# zx80_SD_12_smd_build005.net
KiCad netlist of a schematic drawn in EAGLE
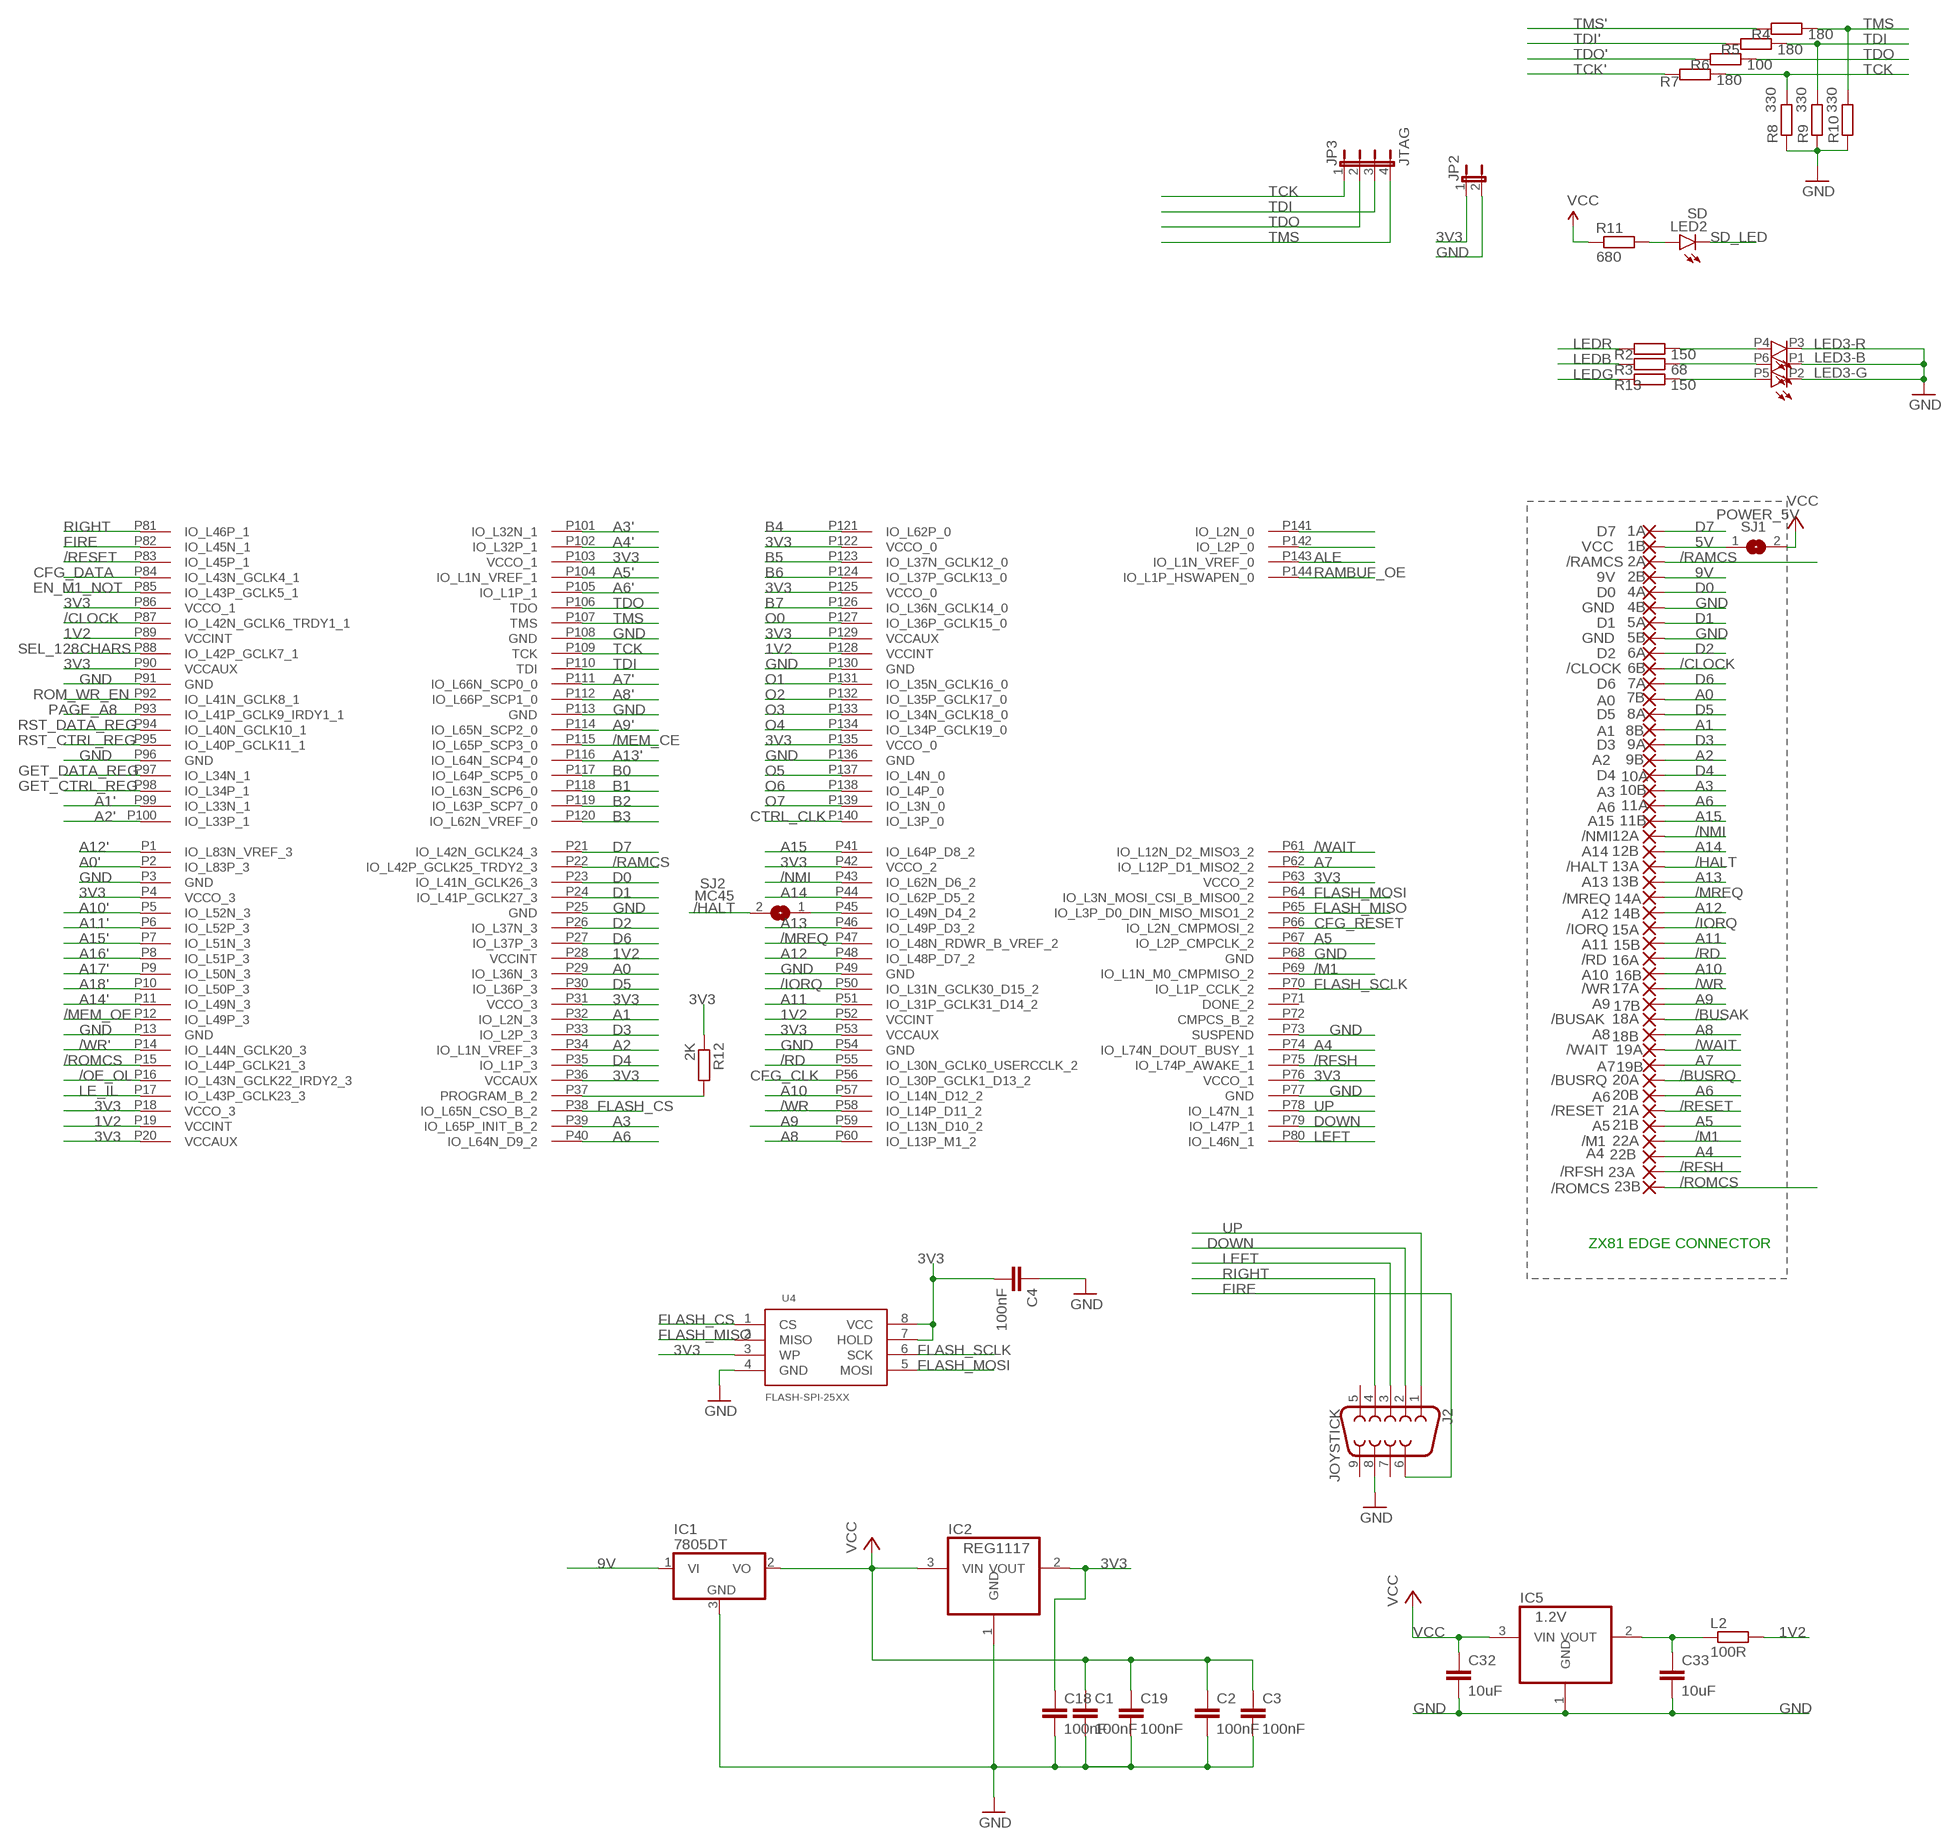
[diagram p0: schematic, sheet 1, part 1 of 2]
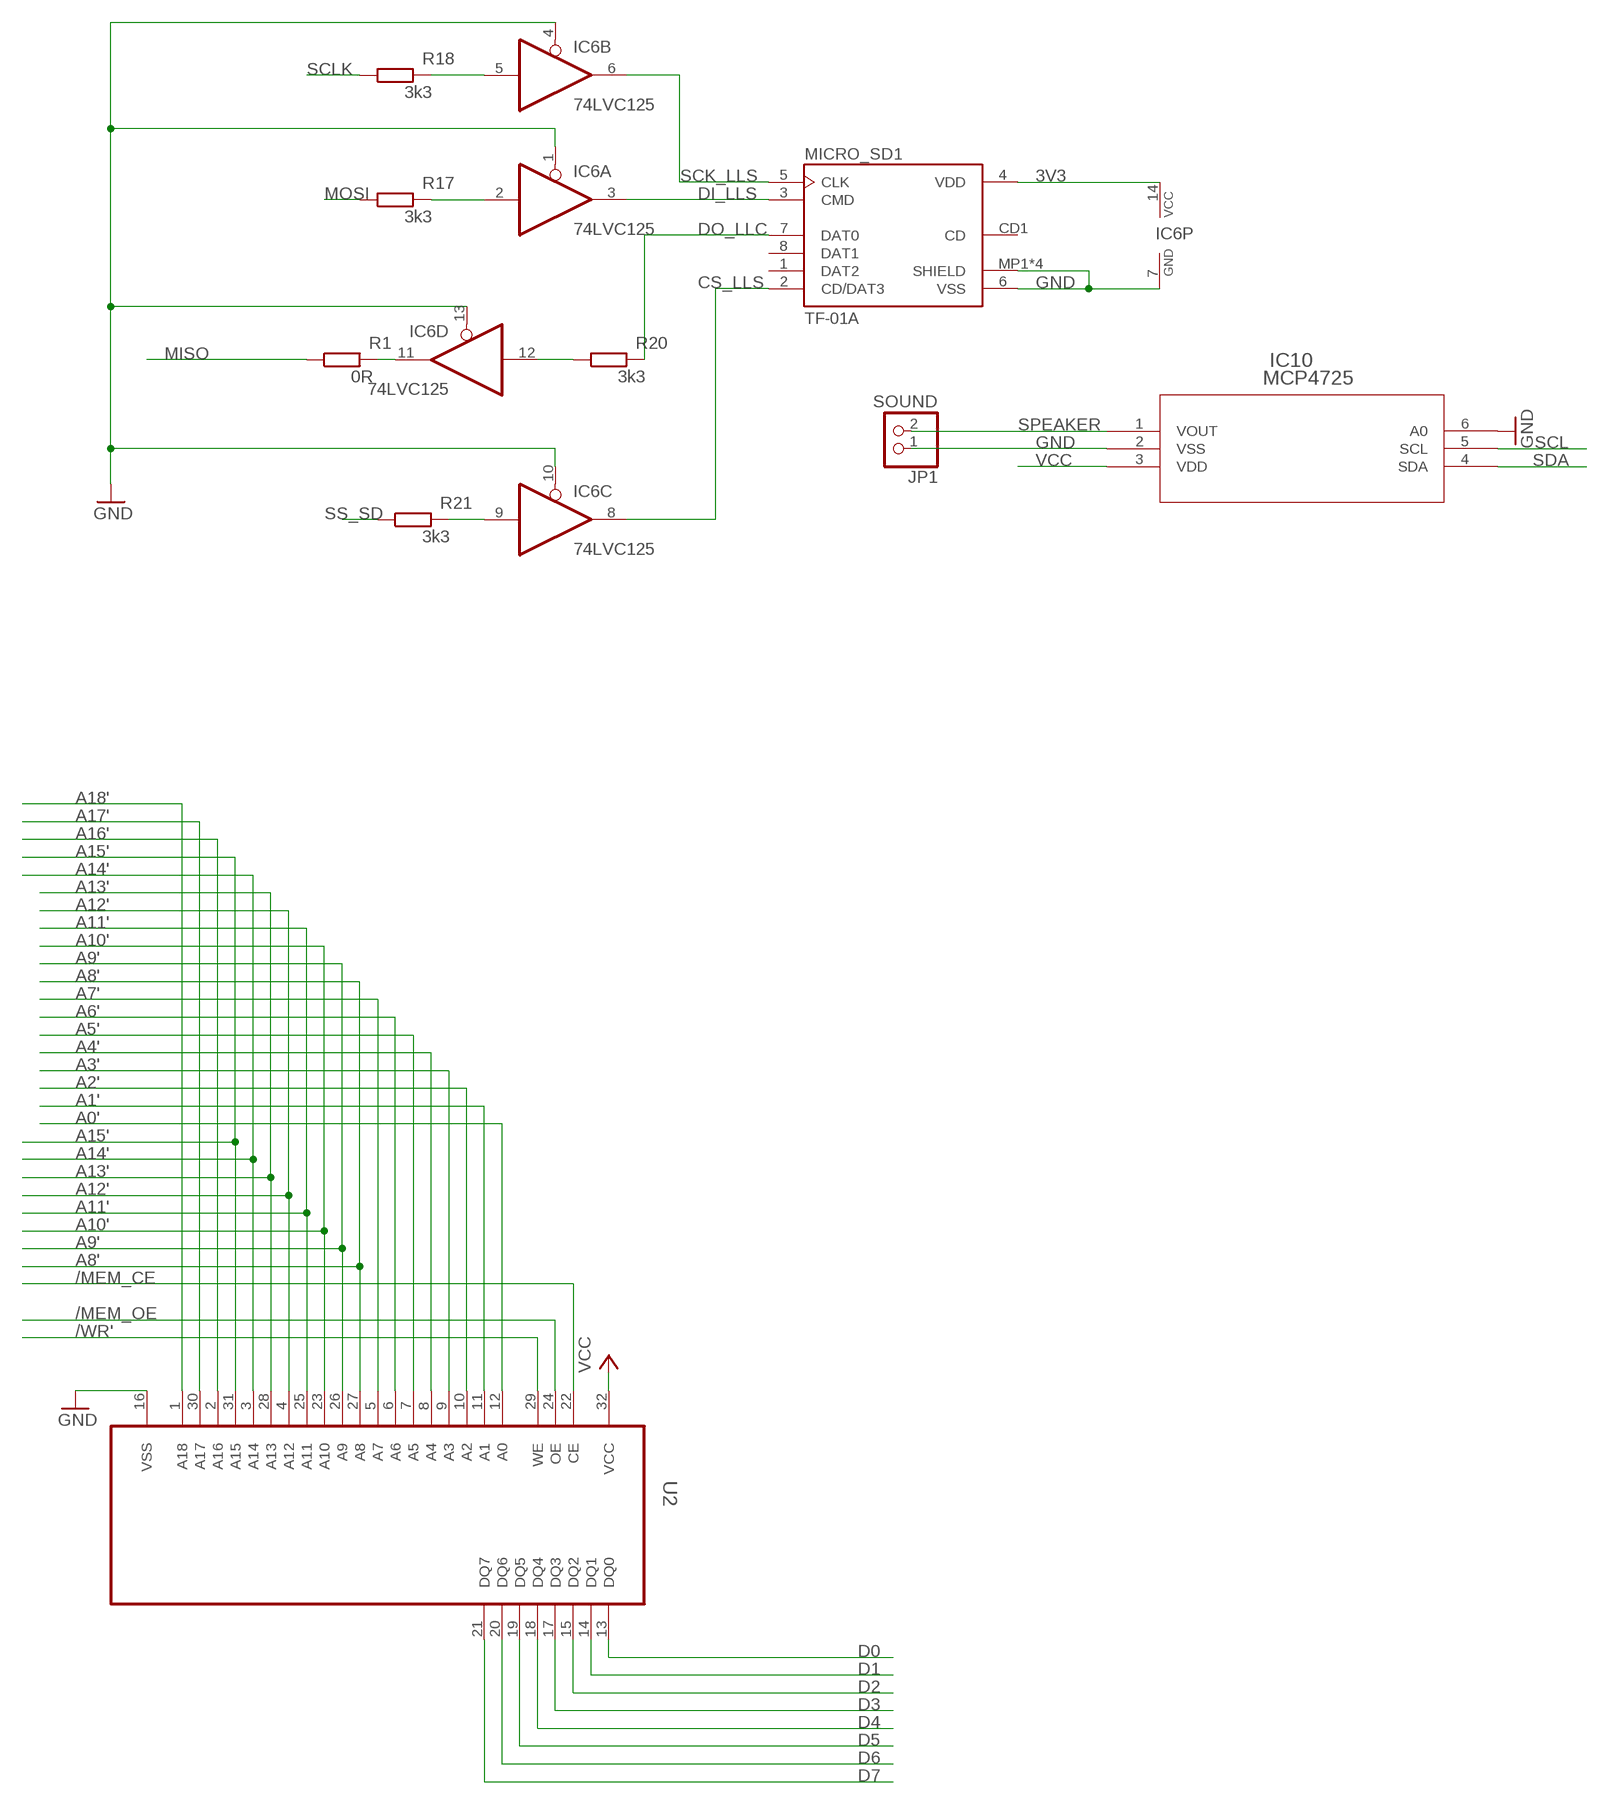
[diagram p1: schematic, sheet 1, part 2 of 2]
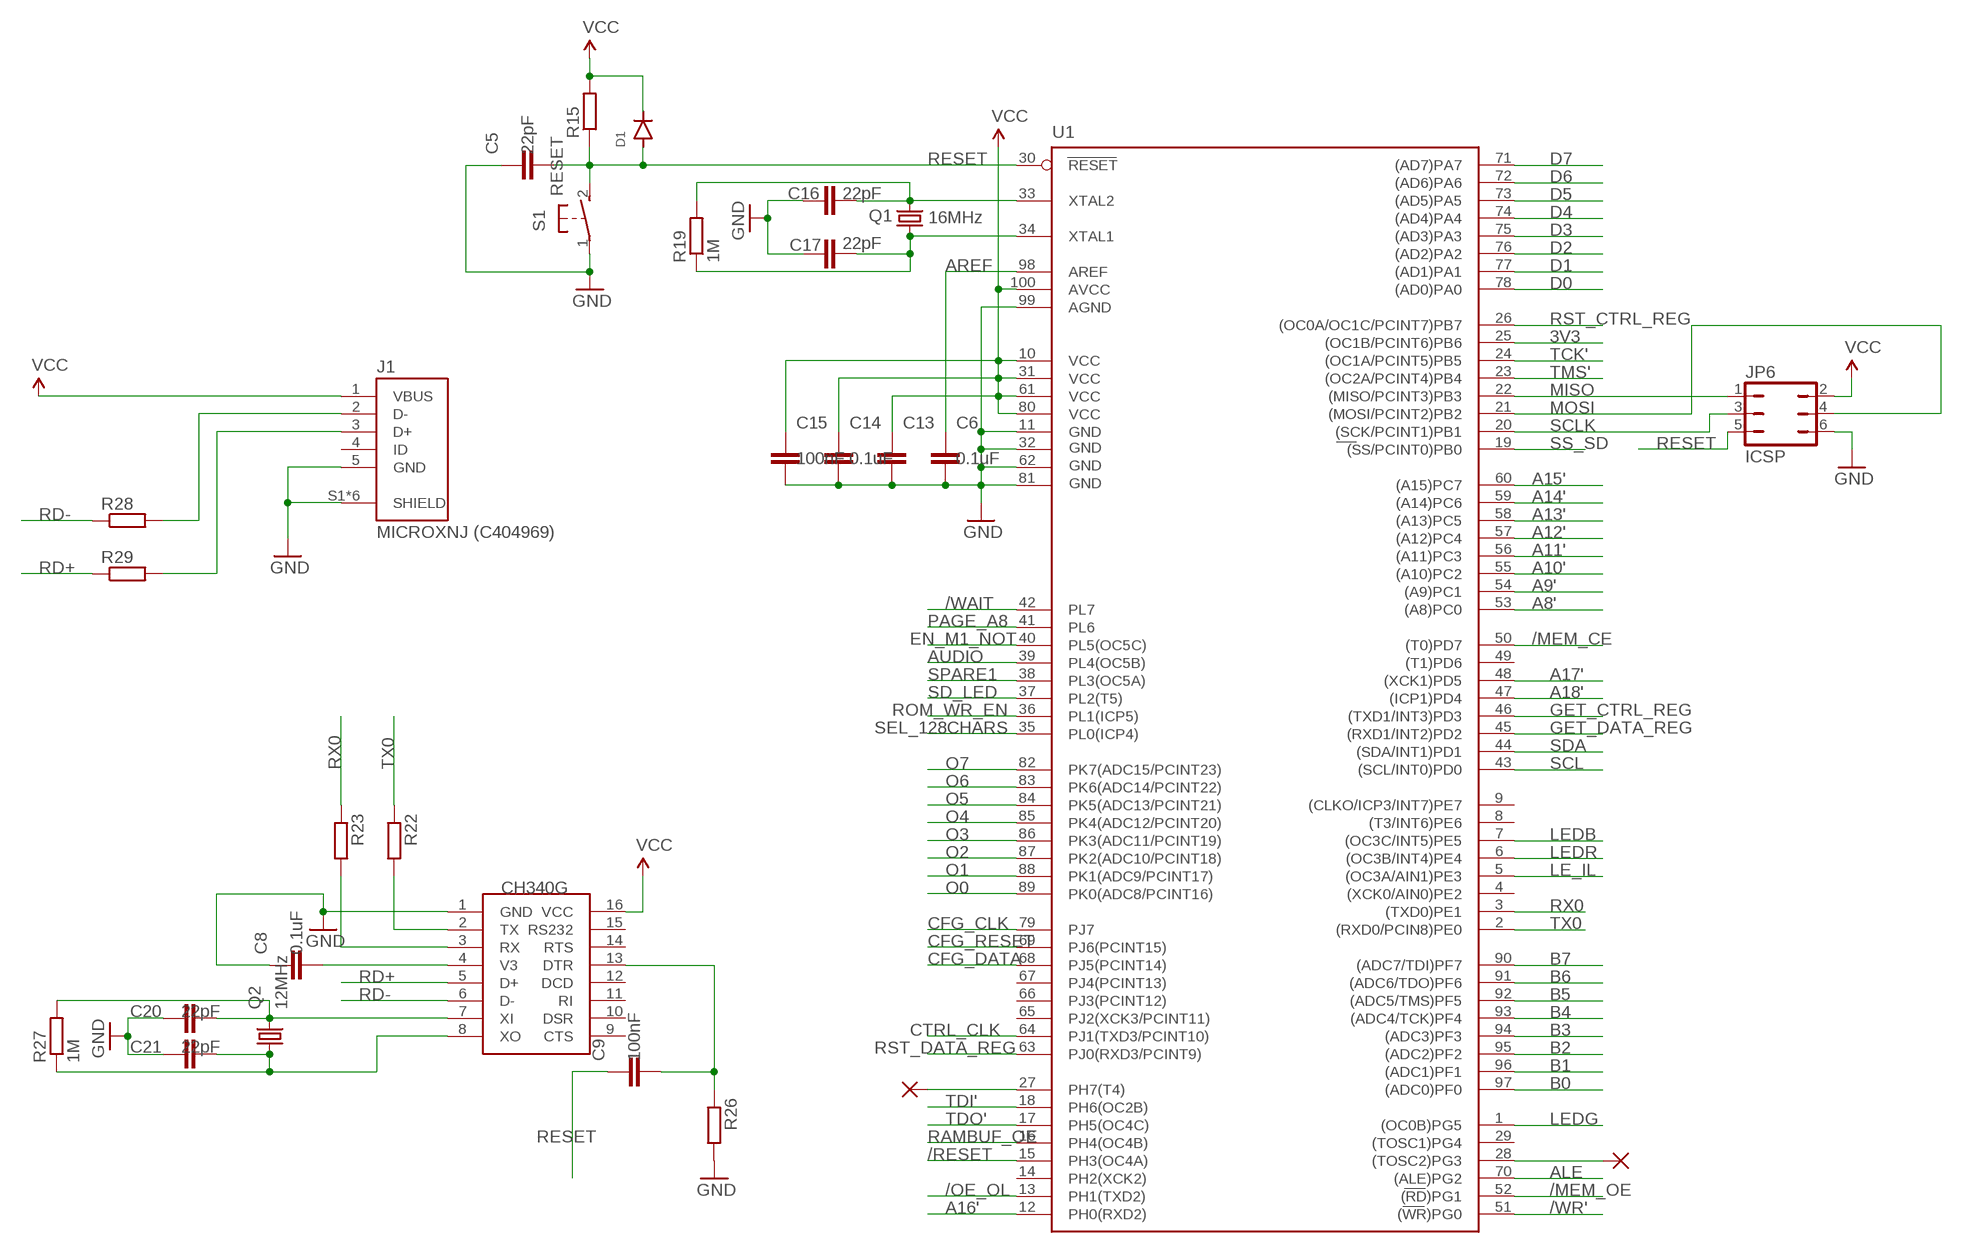
[diagram p2: schematic, sheet 2]

(export (version "E")
  (design (tool "Eeschema 10.0.6"))
  (components
    (comp (ref "1A")
      (value "D7")
      (footprint "eagle-import:EDGEPIN")
      (libsource (lib "eagle-import") (part "SMD2EDGEPIN"))
    )
    (comp (ref "1B")
      (value "VCC")
      (footprint "eagle-import:EDGEPIN")
      (libsource (lib "eagle-import") (part "SMD2EDGEPIN"))
    )
    (comp (ref "2A")
      (value "/RAMCS")
      (footprint "eagle-import:EDGEPIN")
      (libsource (lib "eagle-import") (part "SMD2EDGEPIN"))
    )
    (comp (ref "2B")
      (value "9V")
      (footprint "eagle-import:EDGEPIN")
      (libsource (lib "eagle-import") (part "SMD2EDGEPIN"))
    )
    (comp (ref "4A")
      (value "D0")
      (footprint "eagle-import:EDGEPIN")
      (libsource (lib "eagle-import") (part "SMD2EDGEPIN"))
    )
    (comp (ref "4B")
      (value "GND")
      (footprint "eagle-import:EDGEPIN")
      (libsource (lib "eagle-import") (part "SMD2EDGEPIN"))
    )
    (comp (ref "5A")
      (value "D1")
      (footprint "eagle-import:EDGEPIN")
      (libsource (lib "eagle-import") (part "SMD2EDGEPIN"))
    )
    (comp (ref "5B")
      (value "GND")
      (footprint "eagle-import:EDGEPIN")
      (libsource (lib "eagle-import") (part "SMD2EDGEPIN"))
    )
    (comp (ref "6A")
      (value "D2")
      (footprint "eagle-import:EDGEPIN")
      (libsource (lib "eagle-import") (part "SMD2EDGEPIN"))
    )
    (comp (ref "6B")
      (value "/CLOCK")
      (footprint "eagle-import:EDGEPIN")
      (libsource (lib "eagle-import") (part "SMD2EDGEPIN"))
    )
    (comp (ref "7A")
      (value "D6")
      (footprint "eagle-import:EDGEPIN")
      (libsource (lib "eagle-import") (part "SMD2EDGEPIN"))
    )
    (comp (ref "7B")
      (value "A0")
      (footprint "eagle-import:EDGEPIN")
      (libsource (lib "eagle-import") (part "SMD2EDGEPIN"))
    )
    (comp (ref "8A")
      (value "D5")
      (footprint "eagle-import:EDGEPIN")
      (libsource (lib "eagle-import") (part "SMD2EDGEPIN"))
    )
    (comp (ref "8B")
      (value "A1")
      (footprint "eagle-import:EDGEPIN")
      (libsource (lib "eagle-import") (part "SMD2EDGEPIN"))
    )
    (comp (ref "9A")
      (value "D3")
      (footprint "eagle-import:EDGEPIN")
      (libsource (lib "eagle-import") (part "SMD2EDGEPIN"))
    )
    (comp (ref "9B")
      (value "A2")
      (footprint "eagle-import:EDGEPIN")
      (libsource (lib "eagle-import") (part "SMD2EDGEPIN"))
    )
    (comp (ref "10A")
      (value "D4")
      (footprint "eagle-import:EDGEPIN")
      (libsource (lib "eagle-import") (part "SMD2EDGEPIN"))
    )
    (comp (ref "10B")
      (value "A3")
      (footprint "eagle-import:EDGEPIN")
      (libsource (lib "eagle-import") (part "SMD2EDGEPIN"))
    )
    (comp (ref "11A")
      (value "A6")
      (footprint "eagle-import:EDGEPIN")
      (libsource (lib "eagle-import") (part "SMD2EDGEPIN"))
    )
    (comp (ref "11B")
      (value "A15")
      (footprint "eagle-import:EDGEPIN")
      (libsource (lib "eagle-import") (part "SMD2EDGEPIN"))
    )
    (comp (ref "12A")
      (value "/NMI")
      (footprint "eagle-import:EDGEPIN")
      (libsource (lib "eagle-import") (part "SMD2EDGEPIN"))
    )
    (comp (ref "12B")
      (value "A14")
      (footprint "eagle-import:EDGEPIN")
      (libsource (lib "eagle-import") (part "SMD2EDGEPIN"))
    )
    (comp (ref "13A")
      (value "/HALT")
      (footprint "eagle-import:EDGEPIN")
      (libsource (lib "eagle-import") (part "SMD2EDGEPIN"))
    )
    (comp (ref "13B")
      (value "A13")
      (footprint "eagle-import:EDGEPIN")
      (libsource (lib "eagle-import") (part "SMD2EDGEPIN"))
    )
    (comp (ref "14A")
      (value "/MREQ")
      (footprint "eagle-import:EDGEPIN")
      (libsource (lib "eagle-import") (part "SMD2EDGEPIN"))
    )
    (comp (ref "14B")
      (value "A12")
      (footprint "eagle-import:EDGEPIN")
      (libsource (lib "eagle-import") (part "SMD2EDGEPIN"))
    )
    (comp (ref "15A")
      (value "/IORQ")
      (footprint "eagle-import:EDGEPIN")
      (libsource (lib "eagle-import") (part "SMD2EDGEPIN"))
    )
    (comp (ref "15B")
      (value "A11")
      (footprint "eagle-import:EDGEPIN")
      (libsource (lib "eagle-import") (part "SMD2EDGEPIN"))
    )
    (comp (ref "16A")
      (value "/RD")
      (footprint "eagle-import:EDGEPIN")
      (libsource (lib "eagle-import") (part "SMD2EDGEPIN"))
    )
    (comp (ref "16B")
      (value "A10")
      (footprint "eagle-import:EDGEPIN")
      (libsource (lib "eagle-import") (part "SMD2EDGEPIN"))
    )
    (comp (ref "17A")
      (value "/WR")
      (footprint "eagle-import:EDGEPIN")
      (libsource (lib "eagle-import") (part "SMD2EDGEPIN"))
    )
    (comp (ref "17B")
      (value "A9")
      (footprint "eagle-import:EDGEPIN")
      (libsource (lib "eagle-import") (part "SMD2EDGEPIN"))
    )
    (comp (ref "18A")
      (value "/BUSAK")
      (footprint "eagle-import:EDGEPIN")
      (libsource (lib "eagle-import") (part "SMD2EDGEPIN"))
    )
    (comp (ref "18B")
      (value "A8")
      (footprint "eagle-import:EDGEPIN")
      (libsource (lib "eagle-import") (part "SMD2EDGEPIN"))
    )
    (comp (ref "19A")
      (value "/WAIT")
      (footprint "eagle-import:EDGEPIN")
      (libsource (lib "eagle-import") (part "SMD2EDGEPIN"))
    )
    (comp (ref "19B")
      (value "A7")
      (footprint "eagle-import:EDGEPIN")
      (libsource (lib "eagle-import") (part "SMD2EDGEPIN"))
    )
    (comp (ref "20A")
      (value "/BUSRQ")
      (footprint "eagle-import:EDGEPIN")
      (libsource (lib "eagle-import") (part "SMD2EDGEPIN"))
    )
    (comp (ref "20B")
      (value "A6")
      (footprint "eagle-import:EDGEPIN")
      (libsource (lib "eagle-import") (part "SMD2EDGEPIN"))
    )
    (comp (ref "21A")
      (value "/RESET")
      (footprint "eagle-import:EDGEPIN")
      (libsource (lib "eagle-import") (part "SMD2EDGEPIN"))
    )
    (comp (ref "21B")
      (value "A5")
      (footprint "eagle-import:EDGEPIN")
      (libsource (lib "eagle-import") (part "SMD2EDGEPIN"))
    )
    (comp (ref "22A")
      (value "/M1")
      (footprint "eagle-import:EDGEPIN")
      (libsource (lib "eagle-import") (part "SMD2EDGEPIN"))
    )
    (comp (ref "22B")
      (value "A4")
      (footprint "eagle-import:EDGEPIN")
      (libsource (lib "eagle-import") (part "SMD2EDGEPIN"))
    )
    (comp (ref "23A")
      (value "/RFSH")
      (footprint "eagle-import:EDGEPIN")
      (libsource (lib "eagle-import") (part "SMD2EDGEPIN"))
    )
    (comp (ref "23B")
      (value "/ROMCS")
      (footprint "eagle-import:EDGEPIN")
      (libsource (lib "eagle-import") (part "SMD2EDGEPIN"))
    )
    (comp (ref "C1")
      (value "100nF")
      (footprint "eagle-import:C0603")
      (libsource (lib "eagle-import") (part "rcl_334_C-EUC0603"))
    )
    (comp (ref "C2")
      (value "100nF")
      (footprint "eagle-import:C0603")
      (libsource (lib "eagle-import") (part "rcl_334_C-EUC0603"))
    )
    (comp (ref "C3")
      (value "100nF")
      (footprint "eagle-import:C0603")
      (libsource (lib "eagle-import") (part "rcl_334_C-EUC0603"))
    )
    (comp (ref "C4")
      (value "100nF")
      (footprint "eagle-import:C0603K")
      (libsource (lib "eagle-import") (part "C-EUC0603K"))
    )
    (comp (ref "C18")
      (value "100nF")
      (footprint "eagle-import:C0603")
      (libsource (lib "eagle-import") (part "rcl_334_C-EUC0603"))
    )
    (comp (ref "C19")
      (value "100nF")
      (footprint "eagle-import:C0603")
      (libsource (lib "eagle-import") (part "rcl_334_C-EUC0603"))
    )
    (comp (ref "C32")
      (value "10uF")
      (footprint "eagle-import:C0603K")
      (libsource (lib "eagle-import") (part "C-EUC0603K"))
    )
    (comp (ref "C33")
      (value "10uF")
      (footprint "eagle-import:C0603K")
      (libsource (lib "eagle-import") (part "C-EUC0603K"))
    )
    (comp (ref "IC1")
      (value "7805DT")
      (footprint "eagle-import:TO252")
      (libsource (lib "eagle-import") (part "78DT05"))
    )
    (comp (ref "IC2")
      (value "REG1117")
      (footprint "eagle-import:SOT223")
      (libsource (lib "eagle-import") (part "burr-brown_41243815_REG1117"))
    )
    (comp (ref "IC5")
      (value "1.2V")
      (footprint "eagle-import:SOT223")
      (fields (field (name "MPN") "REG1117"))
      (libsource (lib "eagle-import") (part "REG1117"))
    )
    (comp (ref "IC6")
      (value "74LVC125")
      (footprint "eagle-import:SO14")
      (libsource (lib "eagle-import") (part "74125DLS"))
    )
    (comp (ref "IC10")
      (value "MCP4725")
      (footprint "eagle-import:SOT-23-6_MC")
      (fields (field (name "MF") "Microchip") (field (name "MP") "MCP4725A2T-E/CH"))
      (libsource (lib "eagle-import") (part "MCP4725A2T-E/CH"))
    )
    (comp (ref "J2")
      (value "JOYSTICK")
      (footprint "eagle-import:DB9_MALE")
      (libsource (lib "eagle-import") (part "DB9MALE"))
    )
    (comp (ref "JP1")
      (value "SOUND")
      (footprint "eagle-import:1X02")
      (libsource (lib "eagle-import") (part "PINHD-1X2"))
    )
    (comp (ref "JP2")
      (value "JP1E")
      (footprint "eagle-import:JP1")
      (libsource (lib "eagle-import") (part "JP1E"))
    )
    (comp (ref "JP3")
      (value "JTAG")
      (footprint "eagle-import:JP4")
      (libsource (lib "eagle-import") (part "JP4E"))
    )
    (comp (ref "L2")
      (value "100R")
      (footprint "eagle-import:R0603")
      (libsource (lib "eagle-import") (part "R-EU_R0603"))
    )
    (comp (ref "LED2")
      (value "SD")
      (footprint "eagle-import:CHIPLED_0603")
      (libsource (lib "eagle-import") (part "LEDCHIPLED_0603"))
    )
    (comp (ref "LED3")
      (value "STATUS")
      (footprint "eagle-import:3535-PLCC6")
      (libsource (lib "eagle-import") (part "3535RGB3535RGB"))
    )
    (comp (ref "MICRO_SD1")
      (value "TF-01A")
      (footprint "eagle-import:TF-01A")
      (fields (field (name "MF") "HRO Electronics Co., Ltd."))
      (libsource (lib "eagle-import") (part "TF-01A"))
    )
    (comp (ref "R1")
      (value "0R")
      (footprint "eagle-import:R0603")
      (libsource (lib "eagle-import") (part "R-EU_R0603"))
    )
    (comp (ref "R2")
      (value "150")
      (footprint "eagle-import:R0603")
      (libsource (lib "eagle-import") (part "rcl_334_R-EU_R0603"))
    )
    (comp (ref "R3")
      (value "68")
      (footprint "eagle-import:R0603")
      (libsource (lib "eagle-import") (part "rcl_334_R-EU_R0603"))
    )
    (comp (ref "R4")
      (value "180")
      (footprint "eagle-import:R0603")
      (libsource (lib "eagle-import") (part "rcl_334_R-EU_R0603"))
    )
    (comp (ref "R5")
      (value "180")
      (footprint "eagle-import:R0603")
      (libsource (lib "eagle-import") (part "rcl_334_R-EU_R0603"))
    )
    (comp (ref "R6")
      (value "100")
      (footprint "eagle-import:R0603")
      (libsource (lib "eagle-import") (part "rcl_334_R-EU_R0603"))
    )
    (comp (ref "R7")
      (value "180")
      (footprint "eagle-import:R0603")
      (libsource (lib "eagle-import") (part "rcl_334_R-EU_R0603"))
    )
    (comp (ref "R8")
      (value "330")
      (footprint "eagle-import:R0603")
      (libsource (lib "eagle-import") (part "rcl_334_R-EU_R0603"))
    )
    (comp (ref "R9")
      (value "330")
      (footprint "eagle-import:R0603")
      (libsource (lib "eagle-import") (part "rcl_334_R-EU_R0603"))
    )
    (comp (ref "R10")
      (value "330")
      (footprint "eagle-import:R0603")
      (libsource (lib "eagle-import") (part "rcl_334_R-EU_R0603"))
    )
    (comp (ref "R11")
      (value "680")
      (footprint "eagle-import:R0603")
      (libsource (lib "eagle-import") (part "R-EU_R0603"))
    )
    (comp (ref "R12")
      (value "2K")
      (footprint "eagle-import:R0603")
      (libsource (lib "eagle-import") (part "rcl_334_R-EU_R0603"))
    )
    (comp (ref "R13")
      (value "150")
      (footprint "eagle-import:R0603")
      (libsource (lib "eagle-import") (part "rcl_334_R-EU_R0603"))
    )
    (comp (ref "R17")
      (value "3k3")
      (footprint "eagle-import:R0603")
      (libsource (lib "eagle-import") (part "R-EU_R0603"))
    )
    (comp (ref "R18")
      (value "3k3")
      (footprint "eagle-import:R0603")
      (libsource (lib "eagle-import") (part "R-EU_R0603"))
    )
    (comp (ref "R20")
      (value "3k3")
      (footprint "eagle-import:R0603")
      (libsource (lib "eagle-import") (part "R-EU_R0603"))
    )
    (comp (ref "R21")
      (value "3k3")
      (footprint "eagle-import:R0603")
      (libsource (lib "eagle-import") (part "R-EU_R0603"))
    )
    (comp (ref "SJ1")
      (value "POWER_5V")
      (footprint "eagle-import:SJ")
      (libsource (lib "eagle-import") (part "SJ"))
    )
    (comp (ref "SJ2")
      (value "MC45")
      (footprint "eagle-import:SJ")
      (libsource (lib "eagle-import") (part "SJ"))
    )
    (comp (ref "U$1")
      (value "XC6SLX9-2TQG144C")
      (footprint "eagle-import:TQ144")
      (fields (field (name "MF") "Xilinx Inc."))
      (libsource (lib "eagle-import") (part "XC6SLX9-2TQG144C"))
    )
    (comp (ref "U2")
      (value "AS6C4008")
      (footprint "eagle-import:SOP32-5")
      (libsource (lib "eagle-import") (part "AS6C4008-55SINSOP5"))
    )
    (comp (ref "U4")
      (value "FLASH-SPI-25XX")
      (footprint "eagle-import:SO08-EIAJ")
      (libsource (lib "eagle-import") (part "FLASH-SPI-25XXSMD1"))
    )
    (comp (ref "C5")
      (value "22pF")
      (footprint "eagle-import:C0603")
      (libsource (lib "eagle-import") (part "rcl_334_C-EUC0603"))
    )
    (comp (ref "C6")
      (value "0.1uF")
      (footprint "eagle-import:C0603")
      (libsource (lib "eagle-import") (part "rcl_334_C-EUC0603"))
    )
    (comp (ref "C8")
      (value "0.1uF")
      (footprint "eagle-import:C0603")
      (libsource (lib "eagle-import") (part "rcl_334_C-EUC0603"))
    )
    (comp (ref "C9")
      (value "100nF")
      (footprint "eagle-import:C0603")
      (libsource (lib "eagle-import") (part "rcl_334_C-EUC0603"))
    )
    (comp (ref "C13")
      (value "0.1uF")
      (footprint "eagle-import:C0603")
      (libsource (lib "eagle-import") (part "rcl_334_C-EUC0603"))
    )
    (comp (ref "C14")
      (value "0.1uF")
      (footprint "eagle-import:C0603")
      (libsource (lib "eagle-import") (part "rcl_334_C-EUC0603"))
    )
    (comp (ref "C15")
      (value "100nF")
      (footprint "eagle-import:C0603")
      (libsource (lib "eagle-import") (part "rcl_334_C-EUC0603"))
    )
    (comp (ref "C16")
      (value "22pF")
      (footprint "eagle-import:C0603")
      (libsource (lib "eagle-import") (part "rcl_334_C-EUC0603"))
    )
    (comp (ref "C17")
      (value "22pF")
      (footprint "eagle-import:C0603")
      (libsource (lib "eagle-import") (part "rcl_334_C-EUC0603"))
    )
    (comp (ref "C20")
      (value "22pF")
      (footprint "eagle-import:C0603")
      (libsource (lib "eagle-import") (part "rcl_334_C-EUC0603"))
    )
    (comp (ref "C21")
      (value "22pF")
      (footprint "eagle-import:C0603")
      (libsource (lib "eagle-import") (part "rcl_334_C-EUC0603"))
    )
    (comp (ref "D1")
      (value "DIODE-SOD123")
      (footprint "eagle-import:SOD123")
      (libsource (lib "eagle-import") (part "DIODE-SOD123"))
    )
    (comp (ref "IC7")
      (value "CH340G")
      (footprint "eagle-import:SOIC16")
      (libsource (lib "eagle-import") (part "CH340G"))
    )
    (comp (ref "J1")
      (value "MICROXNJ (C404969)")
      (footprint "eagle-import:SHOUHAN_MICROXNJ")
      (fields (field (name "MF") "Shouhan") (field (name "MP") "MICROXNJ"))
      (libsource (lib "eagle-import") (part "MICROXNJ"))
    )
    (comp (ref "JP6")
      (value "ICSP")
      (footprint "eagle-import:JP3Q")
      (libsource (lib "eagle-import") (part "JP3Q"))
    )
    (comp (ref "PAD2")
      (value "PH7")
      (footprint "eagle-import:1,6_0,8")
      (libsource (lib "eagle-import") (part "1,6/0,8"))
    )
    (comp (ref "PAD3")
      (value "PG3")
      (footprint "eagle-import:1,6_0,8")
      (libsource (lib "eagle-import") (part "1,6/0,8"))
    )
    (comp (ref "Q1")
      (value "16MHz")
      (footprint "eagle-import:3.2X2.5_KX-7")
      (libsource (lib "eagle-import") (part "KX-7"))
    )
    (comp (ref "Q2")
      (value "12MHz")
      (footprint "eagle-import:3.2X2.5_KX-7")
      (libsource (lib "eagle-import") (part "KX-7"))
    )
    (comp (ref "R15")
      (value "R-EU_R0603")
      (footprint "eagle-import:R0603")
      (libsource (lib "eagle-import") (part "rcl_334_R-EU_R0603"))
    )
    (comp (ref "R19")
      (value "1M")
      (footprint "eagle-import:R0603")
      (libsource (lib "eagle-import") (part "rcl_334_R-EU_R0603"))
    )
    (comp (ref "R22")
      (value "1K")
      (footprint "eagle-import:R0603")
      (libsource (lib "eagle-import") (part "rcl_334_R-EU_R0603"))
    )
    (comp (ref "R23")
      (value "1K")
      (footprint "eagle-import:R0603")
      (libsource (lib "eagle-import") (part "rcl_334_R-EU_R0603"))
    )
    (comp (ref "R26")
      (value "1K")
      (footprint "eagle-import:R0603")
      (libsource (lib "eagle-import") (part "rcl_334_R-EU_R0603"))
    )
    (comp (ref "R27")
      (value "1M")
      (footprint "eagle-import:R0603")
      (libsource (lib "eagle-import") (part "rcl_334_R-EU_R0603"))
    )
    (comp (ref "R28")
      (value "22R")
      (footprint "eagle-import:R0603")
      (libsource (lib "eagle-import") (part "rcl_334_R-EU_R0603"))
    )
    (comp (ref "R29")
      (value "22R")
      (footprint "eagle-import:R0603")
      (libsource (lib "eagle-import") (part "rcl_334_R-EU_R0603"))
    )
    (comp (ref "S1")
      (value "RESET")
      (footprint "eagle-import:B3F-31XX")
      (fields (field (name "MPN") "B3F-3100"))
      (libsource (lib "eagle-import") (part "31-XX"))
    )
    (comp (ref "U1")
      (value "ATMEGA2560AU")
      (footprint "eagle-import:TQFP100")
      (libsource (lib "eagle-import") (part "ATMEGA2560AU"))
    )
  )
  (nets
    (net (code "1") (name "1V2") (class "Default")
      (node (ref "L2") (pin "2") (pinfunction "2_2") (pintype "passive"))
      (node (ref "U$1") (pin "P128") (pinfunction "VCCINT_P128") (pintype "bidirectional"))
      (node (ref "U$1") (pin "P19") (pinfunction "VCCINT_P19") (pintype "bidirectional"))
      (node (ref "U$1") (pin "P28") (pinfunction "VCCINT_P28") (pintype "bidirectional"))
      (node (ref "U$1") (pin "P52") (pinfunction "VCCINT_P52") (pintype "bidirectional"))
      (node (ref "U$1") (pin "P89") (pinfunction "VCCINT_P89") (pintype "bidirectional"))
    )
    (net (code "2") (name "3V3") (class "Default")
      (node (ref "C18") (pin "1") (pinfunction "1_1") (pintype "passive"))
      (node (ref "C4") (pin "2") (pinfunction "2_2") (pintype "passive"))
      (node (ref "IC2") (pin "2") (pinfunction "VOUT_2") (pintype "output"))
      (node (ref "IC6") (pin "14") (pinfunction "VCC_14") (pintype "power_in"))
      (node (ref "JP2") (pin "1") (pinfunction "1_1") (pintype "passive"))
      (node (ref "MICRO_SD1") (pin "4") (pinfunction "VDD_4") (pintype "power_in"))
      (node (ref "R12") (pin "1") (pinfunction "1_1") (pintype "passive"))
      (node (ref "U$1") (pin "P103") (pinfunction "VCCO_1_P103") (pintype "bidirectional"))
      (node (ref "U$1") (pin "P122") (pinfunction "VCCO_0_P122") (pintype "bidirectional"))
      (node (ref "U$1") (pin "P125") (pinfunction "VCCO_0_P125") (pintype "bidirectional"))
      (node (ref "U$1") (pin "P129") (pinfunction "VCCAUX_P129") (pintype "bidirectional"))
      (node (ref "U$1") (pin "P135") (pinfunction "VCCO_0_P135") (pintype "bidirectional"))
      (node (ref "U$1") (pin "P18") (pinfunction "VCCO_3_P18") (pintype "bidirectional"))
      (node (ref "U$1") (pin "P20") (pinfunction "VCCAUX_P20") (pintype "bidirectional"))
      (node (ref "U$1") (pin "P31") (pinfunction "VCCO_3_P31") (pintype "bidirectional"))
      (node (ref "U$1") (pin "P36") (pinfunction "VCCAUX_P36") (pintype "bidirectional"))
      (node (ref "U$1") (pin "P4") (pinfunction "VCCO_3_P4") (pintype "bidirectional"))
      (node (ref "U$1") (pin "P42") (pinfunction "VCCO_2_P42") (pintype "bidirectional"))
      (node (ref "U$1") (pin "P53") (pinfunction "VCCAUX_P53") (pintype "bidirectional"))
      (node (ref "U$1") (pin "P63") (pinfunction "VCCO_2_P63") (pintype "bidirectional"))
      (node (ref "U$1") (pin "P76") (pinfunction "VCCO_1_P76") (pintype "bidirectional"))
      (node (ref "U$1") (pin "P86") (pinfunction "VCCO_1_P86") (pintype "bidirectional"))
      (node (ref "U$1") (pin "P90") (pinfunction "VCCAUX_P90") (pintype "bidirectional"))
      (node (ref "U1") (pin "25") (pinfunction "(OC1B/PCINT6)PB6_25") (pintype "bidirectional"))
      (node (ref "U4") (pin "3") (pinfunction "WP_3") (pintype "bidirectional"))
      (node (ref "U4") (pin "7") (pinfunction "HOLD_7") (pintype "bidirectional"))
      (node (ref "U4") (pin "8") (pinfunction "VCC_8") (pintype "bidirectional"))
    )
    (net (code "3") (name "5V") (class "Default")
      (node (ref "1B") (pin "1") (pinfunction "P_1") (pintype "passive"))
      (node (ref "SJ1") (pin "1") (pinfunction "1_1") (pintype "passive"))
    )
    (net (code "4") (name "9V") (class "Default")
      (node (ref "2B") (pin "1") (pinfunction "P_1") (pintype "passive"))
      (node (ref "IC1") (pin "1") (pinfunction "VI_1") (pintype "input"))
    )
    (net (code "5") (name "A0") (class "Default")
      (node (ref "7B") (pin "1") (pinfunction "P_1") (pintype "passive"))
      (node (ref "U$1") (pin "P29") (pinfunction "IO_L36N_3_P29") (pintype "bidirectional"))
    )
    (net (code "6") (name "A0'") (class "Default")
      (node (ref "U$1") (pin "P2") (pinfunction "IO_L83P_3_P2") (pintype "bidirectional"))
      (node (ref "U2") (pin "12") (pinfunction "A0_12") (pintype "input"))
    )
    (net (code "7") (name "A1") (class "Default")
      (node (ref "8B") (pin "1") (pinfunction "P_1") (pintype "passive"))
      (node (ref "U$1") (pin "P32") (pinfunction "IO_L2N_3_P32") (pintype "bidirectional"))
    )
    (net (code "8") (name "A1'") (class "Default")
      (node (ref "U$1") (pin "P99") (pinfunction "IO_L33N_1_P99") (pintype "bidirectional"))
      (node (ref "U2") (pin "11") (pinfunction "A1_11") (pintype "input"))
    )
    (net (code "9") (name "A2") (class "Default")
      (node (ref "9B") (pin "1") (pinfunction "P_1") (pintype "passive"))
      (node (ref "U$1") (pin "P34") (pinfunction "IO_L1N_VREF_3_P34") (pintype "bidirectional"))
    )
    (net (code "10") (name "A2'") (class "Default")
      (node (ref "U$1") (pin "P100") (pinfunction "IO_L33P_1_P100") (pintype "bidirectional"))
      (node (ref "U2") (pin "10") (pinfunction "A2_10") (pintype "input"))
    )
    (net (code "11") (name "A3") (class "Default")
      (node (ref "10B") (pin "1") (pinfunction "P_1") (pintype "passive"))
      (node (ref "U$1") (pin "P39") (pinfunction "IO_L65P_INIT_B_2_P39") (pintype "bidirectional"))
    )
    (net (code "12") (name "A3'") (class "Default")
      (node (ref "U$1") (pin "P101") (pinfunction "IO_L32N_1_P101") (pintype "bidirectional"))
      (node (ref "U2") (pin "9") (pinfunction "A3_9") (pintype "input"))
    )
    (net (code "13") (name "A4") (class "Default")
      (node (ref "22B") (pin "1") (pinfunction "P_1") (pintype "passive"))
      (node (ref "U$1") (pin "P74") (pinfunction "IO_L74N_DOUT_BUSY_1_P74") (pintype "bidirectional"))
    )
    (net (code "14") (name "A4'") (class "Default")
      (node (ref "U$1") (pin "P102") (pinfunction "IO_L32P_1_P102") (pintype "bidirectional"))
      (node (ref "U2") (pin "8") (pinfunction "A4_8") (pintype "input"))
    )
    (net (code "15") (name "A5") (class "Default")
      (node (ref "21B") (pin "1") (pinfunction "P_1") (pintype "passive"))
      (node (ref "U$1") (pin "P67") (pinfunction "IO_L2P_CMPCLK_2_P67") (pintype "bidirectional"))
    )
    (net (code "16") (name "A5'") (class "Default")
      (node (ref "U$1") (pin "P104") (pinfunction "IO_L1N_VREF_1_P104") (pintype "bidirectional"))
      (node (ref "U2") (pin "7") (pinfunction "A5_7") (pintype "input"))
    )
    (net (code "17") (name "A6") (class "Default")
      (node (ref "11A") (pin "1") (pinfunction "P_1") (pintype "passive"))
      (node (ref "20B") (pin "1") (pinfunction "P_1") (pintype "passive"))
      (node (ref "U$1") (pin "P40") (pinfunction "IO_L64N_D9_2_P40") (pintype "bidirectional"))
    )
    (net (code "18") (name "A6'") (class "Default")
      (node (ref "U$1") (pin "P105") (pinfunction "IO_L1P_1_P105") (pintype "bidirectional"))
      (node (ref "U2") (pin "6") (pinfunction "A6_6") (pintype "input"))
    )
    (net (code "19") (name "A7") (class "Default")
      (node (ref "19B") (pin "1") (pinfunction "P_1") (pintype "passive"))
      (node (ref "U$1") (pin "P62") (pinfunction "IO_L12P_D1_MISO2_2_P62") (pintype "bidirectional"))
    )
    (net (code "20") (name "A7'") (class "Default")
      (node (ref "U$1") (pin "P111") (pinfunction "IO_L66N_SCP0_0_P111") (pintype "bidirectional"))
      (node (ref "U2") (pin "5") (pinfunction "A7_5") (pintype "input"))
    )
    (net (code "21") (name "A8") (class "Default")
      (node (ref "18B") (pin "1") (pinfunction "P_1") (pintype "passive"))
      (node (ref "U$1") (pin "P60") (pinfunction "IO_L13P_M1_2_P60") (pintype "bidirectional"))
    )
    (net (code "22") (name "A8'") (class "Default")
      (node (ref "U$1") (pin "P112") (pinfunction "IO_L66P_SCP1_0_P112") (pintype "bidirectional"))
      (node (ref "U1") (pin "53") (pinfunction "(A8)PC0_53") (pintype "bidirectional"))
      (node (ref "U2") (pin "27") (pinfunction "A8_27") (pintype "input"))
    )
    (net (code "23") (name "A9") (class "Default")
      (node (ref "17B") (pin "1") (pinfunction "P_1") (pintype "passive"))
      (node (ref "U$1") (pin "P59") (pinfunction "IO_L13N_D10_2_P59") (pintype "bidirectional"))
    )
    (net (code "24") (name "A9'") (class "Default")
      (node (ref "U$1") (pin "P114") (pinfunction "IO_L65N_SCP2_0_P114") (pintype "bidirectional"))
      (node (ref "U1") (pin "54") (pinfunction "(A9)PC1_54") (pintype "bidirectional"))
      (node (ref "U2") (pin "26") (pinfunction "A9_26") (pintype "input"))
    )
    (net (code "25") (name "A10") (class "Default")
      (node (ref "16B") (pin "1") (pinfunction "P_1") (pintype "passive"))
      (node (ref "U$1") (pin "P57") (pinfunction "IO_L14N_D12_2_P57") (pintype "bidirectional"))
    )
    (net (code "26") (name "A10'") (class "Default")
      (node (ref "U$1") (pin "P5") (pinfunction "IO_L52N_3_P5") (pintype "bidirectional"))
      (node (ref "U1") (pin "55") (pinfunction "(A10)PC2_55") (pintype "bidirectional"))
      (node (ref "U2") (pin "23") (pinfunction "A10_23") (pintype "input"))
    )
    (net (code "27") (name "A11") (class "Default")
      (node (ref "15B") (pin "1") (pinfunction "P_1") (pintype "passive"))
      (node (ref "U$1") (pin "P51") (pinfunction "IO_L31P_GCLK31_D14_2_P51") (pintype "bidirectional"))
    )
    (net (code "28") (name "A11'") (class "Default")
      (node (ref "U$1") (pin "P6") (pinfunction "IO_L52P_3_P6") (pintype "bidirectional"))
      (node (ref "U1") (pin "56") (pinfunction "(A11)PC3_56") (pintype "bidirectional"))
      (node (ref "U2") (pin "25") (pinfunction "A11_25") (pintype "input"))
    )
    (net (code "29") (name "A12") (class "Default")
      (node (ref "14B") (pin "1") (pinfunction "P_1") (pintype "passive"))
      (node (ref "U$1") (pin "P48") (pinfunction "IO_L48P_D7_2_P48") (pintype "bidirectional"))
    )
    (net (code "30") (name "A12'") (class "Default")
      (node (ref "U$1") (pin "P1") (pinfunction "IO_L83N_VREF_3_P1") (pintype "bidirectional"))
      (node (ref "U1") (pin "57") (pinfunction "(A12)PC4_57") (pintype "bidirectional"))
      (node (ref "U2") (pin "4") (pinfunction "A12_4") (pintype "input"))
    )
    (net (code "31") (name "A13") (class "Default")
      (node (ref "13B") (pin "1") (pinfunction "P_1") (pintype "passive"))
      (node (ref "U$1") (pin "P46") (pinfunction "IO_L49P_D3_2_P46") (pintype "bidirectional"))
    )
    (net (code "32") (name "A13'") (class "Default")
      (node (ref "U$1") (pin "P116") (pinfunction "IO_L64N_SCP4_0_P116") (pintype "bidirectional"))
      (node (ref "U1") (pin "58") (pinfunction "(A13)PC5_58") (pintype "bidirectional"))
      (node (ref "U2") (pin "28") (pinfunction "A13_28") (pintype "input"))
    )
    (net (code "33") (name "A14") (class "Default")
      (node (ref "12B") (pin "1") (pinfunction "P_1") (pintype "passive"))
      (node (ref "U$1") (pin "P44") (pinfunction "IO_L62P_D5_2_P44") (pintype "bidirectional"))
    )
    (net (code "34") (name "A14'") (class "Default")
      (node (ref "U$1") (pin "P11") (pinfunction "IO_L49N_3_P11") (pintype "bidirectional"))
      (node (ref "U1") (pin "59") (pinfunction "(A14)PC6_59") (pintype "bidirectional"))
      (node (ref "U2") (pin "3") (pinfunction "A14_3") (pintype "input"))
    )
    (net (code "35") (name "A15") (class "Default")
      (node (ref "11B") (pin "1") (pinfunction "P_1") (pintype "passive"))
      (node (ref "U$1") (pin "P41") (pinfunction "IO_L64P_D8_2_P41") (pintype "bidirectional"))
    )
    (net (code "36") (name "A15'") (class "Default")
      (node (ref "U$1") (pin "P7") (pinfunction "IO_L51N_3_P7") (pintype "bidirectional"))
      (node (ref "U1") (pin "60") (pinfunction "(A15)PC7_60") (pintype "bidirectional"))
      (node (ref "U2") (pin "31") (pinfunction "A15_31") (pintype "input"))
    )
    (net (code "37") (name "A16'") (class "Default")
      (node (ref "U$1") (pin "P8") (pinfunction "IO_L51P_3_P8") (pintype "bidirectional"))
      (node (ref "U1") (pin "12") (pinfunction "PH0(RXD2)_12") (pintype "bidirectional"))
      (node (ref "U2") (pin "2") (pinfunction "A16_2") (pintype "input"))
    )
    (net (code "38") (name "A17'") (class "Default")
      (node (ref "U$1") (pin "P9") (pinfunction "IO_L50N_3_P9") (pintype "bidirectional"))
      (node (ref "U1") (pin "48") (pinfunction "(XCK1)PD5_48") (pintype "bidirectional"))
      (node (ref "U2") (pin "30") (pinfunction "A17_30") (pintype "input"))
    )
    (net (code "39") (name "A18'") (class "Default")
      (node (ref "U$1") (pin "P10") (pinfunction "IO_L50P_3_P10") (pintype "bidirectional"))
      (node (ref "U1") (pin "47") (pinfunction "(ICP1)PD4_47") (pintype "bidirectional"))
      (node (ref "U2") (pin "1") (pinfunction "A18_1") (pintype "input"))
    )
    (net (code "40") (name "ALE") (class "Default")
      (node (ref "U$1") (pin "P143") (pinfunction "IO_L1N_VREF_0_P143") (pintype "bidirectional"))
      (node (ref "U1") (pin "70") (pinfunction "(ALE)PG2_70") (pintype "bidirectional"))
    )
    (net (code "41") (name "AREF") (class "Default")
      (node (ref "C6") (pin "1") (pinfunction "1_1") (pintype "passive"))
      (node (ref "U1") (pin "98") (pinfunction "AREF_98") (pintype "bidirectional"))
    )
    (net (code "42") (name "AUDIO") (class "Default")
      (node (ref "U1") (pin "39") (pinfunction "PL4(OC5B)_39") (pintype "bidirectional"))
    )
    (net (code "43") (name "B0") (class "Default")
      (node (ref "U$1") (pin "P117") (pinfunction "IO_L64P_SCP5_0_P117") (pintype "bidirectional"))
      (node (ref "U1") (pin "97") (pinfunction "(ADC0)PF0_97") (pintype "bidirectional"))
    )
    (net (code "44") (name "B1") (class "Default")
      (node (ref "U$1") (pin "P118") (pinfunction "IO_L63N_SCP6_0_P118") (pintype "bidirectional"))
      (node (ref "U1") (pin "96") (pinfunction "(ADC1)PF1_96") (pintype "bidirectional"))
    )
    (net (code "45") (name "B2") (class "Default")
      (node (ref "U$1") (pin "P119") (pinfunction "IO_L63P_SCP7_0_P119") (pintype "bidirectional"))
      (node (ref "U1") (pin "95") (pinfunction "(ADC2)PF2_95") (pintype "bidirectional"))
    )
    (net (code "46") (name "B3") (class "Default")
      (node (ref "U$1") (pin "P120") (pinfunction "IO_L62N_VREF_0_P120") (pintype "bidirectional"))
      (node (ref "U1") (pin "94") (pinfunction "(ADC3)PF3_94") (pintype "bidirectional"))
    )
    (net (code "47") (name "B4") (class "Default")
      (node (ref "U$1") (pin "P121") (pinfunction "IO_L62P_0_P121") (pintype "bidirectional"))
      (node (ref "U1") (pin "93") (pinfunction "(ADC4/TCK)PF4_93") (pintype "bidirectional"))
    )
    (net (code "48") (name "B5") (class "Default")
      (node (ref "U$1") (pin "P123") (pinfunction "IO_L37N_GCLK12_0_P123") (pintype "bidirectional"))
      (node (ref "U1") (pin "92") (pinfunction "(ADC5/TMS)PF5_92") (pintype "bidirectional"))
    )
    (net (code "49") (name "B6") (class "Default")
      (node (ref "U$1") (pin "P124") (pinfunction "IO_L37P_GCLK13_0_P124") (pintype "bidirectional"))
      (node (ref "U1") (pin "91") (pinfunction "(ADC6/TDO)PF6_91") (pintype "bidirectional"))
    )
    (net (code "50") (name "B7") (class "Default")
      (node (ref "U$1") (pin "P126") (pinfunction "IO_L36N_GCLK14_0_P126") (pintype "bidirectional"))
      (node (ref "U1") (pin "90") (pinfunction "(ADC7/TDI)PF7_90") (pintype "bidirectional"))
    )
    (net (code "51") (name "CFG_CLK") (class "Default")
      (node (ref "U$1") (pin "P56") (pinfunction "IO_L30P_GCLK1_D13_2_P56") (pintype "bidirectional"))
      (node (ref "U1") (pin "79") (pinfunction "PJ7_79") (pintype "bidirectional"))
    )
    (net (code "52") (name "CFG_DATA") (class "Default")
      (node (ref "U$1") (pin "P84") (pinfunction "IO_L43N_GCLK4_1_P84") (pintype "bidirectional"))
      (node (ref "U1") (pin "68") (pinfunction "PJ5(PCINT14)_68") (pintype "bidirectional"))
    )
    (net (code "53") (name "CFG_RESET") (class "Default")
      (node (ref "U$1") (pin "P66") (pinfunction "IO_L2N_CMPMOSI_2_P66") (pintype "bidirectional"))
      (node (ref "U1") (pin "69") (pinfunction "PJ6(PCINT15)_69") (pintype "bidirectional"))
    )
    (net (code "54") (name "CS_LLS") (class "Default")
      (node (ref "IC6") (pin "8") (pinfunction "O_8") (pintype "tri_state"))
      (node (ref "MICRO_SD1") (pin "2") (pinfunction "CD/DAT3_2") (pintype "bidirectional"))
    )
    (net (code "55") (name "CTRL_CLK") (class "Default")
      (node (ref "U$1") (pin "P140") (pinfunction "IO_L3P_0_P140") (pintype "bidirectional"))
      (node (ref "U1") (pin "64") (pinfunction "PJ1(TXD3/PCINT10)_64") (pintype "bidirectional"))
    )
    (net (code "56") (name "D0") (class "Default")
      (node (ref "4A") (pin "1") (pinfunction "P_1") (pintype "passive"))
      (node (ref "U$1") (pin "P23") (pinfunction "IO_L41N_GCLK26_3_P23") (pintype "bidirectional"))
      (node (ref "U1") (pin "78") (pinfunction "(AD0)PA0_78") (pintype "bidirectional"))
      (node (ref "U2") (pin "13") (pinfunction "DQ0_13") (pintype "output"))
    )
    (net (code "57") (name "D1") (class "Default")
      (node (ref "5A") (pin "1") (pinfunction "P_1") (pintype "passive"))
      (node (ref "U$1") (pin "P24") (pinfunction "IO_L41P_GCLK27_3_P24") (pintype "bidirectional"))
      (node (ref "U1") (pin "77") (pinfunction "(AD1)PA1_77") (pintype "bidirectional"))
      (node (ref "U2") (pin "14") (pinfunction "DQ1_14") (pintype "output"))
    )
    (net (code "58") (name "D2") (class "Default")
      (node (ref "6A") (pin "1") (pinfunction "P_1") (pintype "passive"))
      (node (ref "U$1") (pin "P26") (pinfunction "IO_L37N_3_P26") (pintype "bidirectional"))
      (node (ref "U1") (pin "76") (pinfunction "(AD2)PA2_76") (pintype "bidirectional"))
      (node (ref "U2") (pin "15") (pinfunction "DQ2_15") (pintype "output"))
    )
    (net (code "59") (name "D3") (class "Default")
      (node (ref "9A") (pin "1") (pinfunction "P_1") (pintype "passive"))
      (node (ref "U$1") (pin "P33") (pinfunction "IO_L2P_3_P33") (pintype "bidirectional"))
      (node (ref "U1") (pin "75") (pinfunction "(AD3)PA3_75") (pintype "bidirectional"))
      (node (ref "U2") (pin "17") (pinfunction "DQ3_17") (pintype "output"))
    )
    (net (code "60") (name "D4") (class "Default")
      (node (ref "10A") (pin "1") (pinfunction "P_1") (pintype "passive"))
      (node (ref "U$1") (pin "P35") (pinfunction "IO_L1P_3_P35") (pintype "bidirectional"))
      (node (ref "U1") (pin "74") (pinfunction "(AD4)PA4_74") (pintype "bidirectional"))
      (node (ref "U2") (pin "18") (pinfunction "DQ4_18") (pintype "output"))
    )
    (net (code "61") (name "D5") (class "Default")
      (node (ref "8A") (pin "1") (pinfunction "P_1") (pintype "passive"))
      (node (ref "U$1") (pin "P30") (pinfunction "IO_L36P_3_P30") (pintype "bidirectional"))
      (node (ref "U1") (pin "73") (pinfunction "(AD5)PA5_73") (pintype "bidirectional"))
      (node (ref "U2") (pin "19") (pinfunction "DQ5_19") (pintype "output"))
    )
    (net (code "62") (name "D6") (class "Default")
      (node (ref "7A") (pin "1") (pinfunction "P_1") (pintype "passive"))
      (node (ref "U$1") (pin "P27") (pinfunction "IO_L37P_3_P27") (pintype "bidirectional"))
      (node (ref "U1") (pin "72") (pinfunction "(AD6)PA6_72") (pintype "bidirectional"))
      (node (ref "U2") (pin "20") (pinfunction "DQ6_20") (pintype "output"))
    )
    (net (code "63") (name "D7") (class "Default")
      (node (ref "1A") (pin "1") (pinfunction "P_1") (pintype "passive"))
      (node (ref "U$1") (pin "P21") (pinfunction "IO_L42N_GCLK24_3_P21") (pintype "bidirectional"))
      (node (ref "U1") (pin "71") (pinfunction "(AD7)PA7_71") (pintype "bidirectional"))
      (node (ref "U2") (pin "21") (pinfunction "DQ7_21") (pintype "output"))
    )
    (net (code "64") (name "DI_LLS") (class "Default")
      (node (ref "IC6") (pin "3") (pinfunction "O_3") (pintype "tri_state"))
      (node (ref "MICRO_SD1") (pin "3") (pinfunction "CMD_3") (pintype "bidirectional"))
    )
    (net (code "65") (name "DOWN") (class "Default")
      (node (ref "J2") (pin "2") (pinfunction "2_2") (pintype "passive"))
      (node (ref "U$1") (pin "P79") (pinfunction "IO_L47P_1_P79") (pintype "bidirectional"))
    )
    (net (code "66") (name "DO_LLC") (class "Default")
      (node (ref "IC6") (pin "12") (pinfunction "I_12") (pintype "input"))
      (node (ref "R20") (pin "1") (pinfunction "1_1") (pintype "passive"))
    )
    (net (code "67") (name "EN_M1_NOT") (class "Default")
      (node (ref "U$1") (pin "P85") (pinfunction "IO_L43P_GCLK5_1_P85") (pintype "bidirectional"))
      (node (ref "U1") (pin "40") (pinfunction "PL5(OC5C)_40") (pintype "bidirectional"))
    )
    (net (code "68") (name "FIRE") (class "Default")
      (node (ref "J2") (pin "6") (pinfunction "6_6") (pintype "passive"))
      (node (ref "U$1") (pin "P82") (pinfunction "IO_L45N_1_P82") (pintype "bidirectional"))
    )
    (net (code "69") (name "FLASH_CS") (class "Default")
      (node (ref "U$1") (pin "P38") (pinfunction "IO_L65N_CSO_B_2_P38") (pintype "bidirectional"))
      (node (ref "U4") (pin "1") (pinfunction "CS_1") (pintype "bidirectional"))
    )
    (net (code "70") (name "FLASH_MISO") (class "Default")
      (node (ref "U$1") (pin "P65") (pinfunction "IO_L3P_D0_DIN_MISO_MISO1_2_P65") (pintype "bidirectional"))
      (node (ref "U4") (pin "2") (pinfunction "MISO_2") (pintype "bidirectional"))
    )
    (net (code "71") (name "FLASH_MOSI") (class "Default")
      (node (ref "U$1") (pin "P64") (pinfunction "IO_L3N_MOSI_CSI_B_MISO0_2_P64") (pintype "bidirectional"))
      (node (ref "U4") (pin "5") (pinfunction "MOSI_5") (pintype "bidirectional"))
    )
    (net (code "72") (name "FLASH_SCLK") (class "Default")
      (node (ref "U$1") (pin "P70") (pinfunction "IO_L1P_CCLK_2_P70") (pintype "bidirectional"))
      (node (ref "U4") (pin "6") (pinfunction "SCK_6") (pintype "bidirectional"))
    )
    (net (code "73") (name "GET_CTRL_REG") (class "Default")
      (node (ref "U$1") (pin "P98") (pinfunction "IO_L34P_1_P98") (pintype "bidirectional"))
      (node (ref "U1") (pin "46") (pinfunction "(TXD1/INT3)PD3_46") (pintype "bidirectional"))
    )
    (net (code "74") (name "GET_DATA_REG") (class "Default")
      (node (ref "U$1") (pin "P97") (pinfunction "IO_L34N_1_P97") (pintype "bidirectional"))
      (node (ref "U1") (pin "45") (pinfunction "(RXD1/INT2)PD2_45") (pintype "bidirectional"))
    )
    (net (code "75") (name "GND") (class "Default")
      (node (ref "4B") (pin "1") (pinfunction "P_1") (pintype "passive"))
      (node (ref "5B") (pin "1") (pinfunction "P_1") (pintype "passive"))
      (node (ref "C1") (pin "2") (pinfunction "2_2") (pintype "passive"))
      (node (ref "C13") (pin "2") (pinfunction "2_2") (pintype "passive"))
      (node (ref "C14") (pin "2") (pinfunction "2_2") (pintype "passive"))
      (node (ref "C15") (pin "2") (pinfunction "2_2") (pintype "passive"))
      (node (ref "C16") (pin "1") (pinfunction "1_1") (pintype "passive"))
      (node (ref "C17") (pin "1") (pinfunction "1_1") (pintype "passive"))
      (node (ref "C18") (pin "2") (pinfunction "2_2") (pintype "passive"))
      (node (ref "C19") (pin "2") (pinfunction "2_2") (pintype "passive"))
      (node (ref "C2") (pin "2") (pinfunction "2_2") (pintype "passive"))
      (node (ref "C20") (pin "1") (pinfunction "1_1") (pintype "passive"))
      (node (ref "C21") (pin "1") (pinfunction "1_1") (pintype "passive"))
      (node (ref "C3") (pin "2") (pinfunction "2_2") (pintype "passive"))
      (node (ref "C32") (pin "2") (pinfunction "2_2") (pintype "passive"))
      (node (ref "C33") (pin "2") (pinfunction "2_2") (pintype "passive"))
      (node (ref "C4") (pin "1") (pinfunction "1_1") (pintype "passive"))
      (node (ref "C5") (pin "1") (pinfunction "1_1") (pintype "passive"))
      (node (ref "C6") (pin "2") (pinfunction "2_2") (pintype "passive"))
      (node (ref "C8") (pin "1") (pinfunction "1_1") (pintype "passive"))
      (node (ref "IC1") (pin "3") (pinfunction "GND_3") (pintype "passive"))
      (node (ref "IC10") (pin "2") (pinfunction "VSS_2") (pintype "passive"))
      (node (ref "IC10") (pin "6") (pinfunction "A0_6") (pintype "passive"))
      (node (ref "IC2") (pin "1") (pinfunction "GND_1") (pintype "power_in"))
      (node (ref "IC5") (pin "1") (pinfunction "GND_1") (pintype "power_in"))
      (node (ref "IC6") (pin "1") (pinfunction "OE_1") (pintype "input"))
      (node (ref "IC6") (pin "10") (pinfunction "OE_10") (pintype "input"))
      (node (ref "IC6") (pin "13") (pinfunction "OE_13") (pintype "input"))
      (node (ref "IC6") (pin "4") (pinfunction "OE_4") (pintype "input"))
      (node (ref "IC6") (pin "7") (pinfunction "GND_7") (pintype "power_in"))
      (node (ref "IC7") (pin "1") (pinfunction "GND_1") (pintype "bidirectional"))
      (node (ref "J1") (pin "5") (pinfunction "GND_5") (pintype "power_in"))
      (node (ref "J1") (pin "S1") (pinfunction "SHIELD_S1") (pintype "passive"))
      (node (ref "J1") (pin "S2") (pinfunction "SHIELD_S2") (pintype "passive"))
      (node (ref "J1") (pin "S3") (pinfunction "SHIELD_S3") (pintype "passive"))
      (node (ref "J1") (pin "S4") (pinfunction "SHIELD_S4") (pintype "passive"))
      (node (ref "J1") (pin "S5") (pinfunction "SHIELD_S5") (pintype "passive"))
      (node (ref "J1") (pin "S6") (pinfunction "SHIELD_S6") (pintype "passive"))
      (node (ref "J2") (pin "8") (pinfunction "8_8") (pintype "passive"))
      (node (ref "JP1") (pin "1") (pinfunction "1_1") (pintype "passive"))
      (node (ref "JP2") (pin "2") (pinfunction "2_2") (pintype "passive"))
      (node (ref "JP6") (pin "6") (pinfunction "6_6") (pintype "passive"))
      (node (ref "LED3") (pin "P1") (pinfunction "C_P1") (pintype "passive"))
      (node (ref "LED3") (pin "P2") (pinfunction "C_P2") (pintype "passive"))
      (node (ref "LED3") (pin "P3") (pinfunction "C_P3") (pintype "passive"))
      (node (ref "MICRO_SD1") (pin "6") (pinfunction "VSS_6") (pintype "power_in"))
      (node (ref "MICRO_SD1") (pin "MP1") (pinfunction "SHIELD_MP1") (pintype "power_in"))
      (node (ref "MICRO_SD1") (pin "MP2") (pinfunction "SHIELD_MP2") (pintype "power_in"))
      (node (ref "MICRO_SD1") (pin "MP3") (pinfunction "SHIELD_MP3") (pintype "power_in"))
      (node (ref "MICRO_SD1") (pin "MP4") (pinfunction "SHIELD_MP4") (pintype "power_in"))
      (node (ref "R10") (pin "1") (pinfunction "1_1") (pintype "passive"))
      (node (ref "R26") (pin "2") (pinfunction "2_2") (pintype "passive"))
      (node (ref "R8") (pin "1") (pinfunction "1_1") (pintype "passive"))
      (node (ref "R9") (pin "1") (pinfunction "1_1") (pintype "passive"))
      (node (ref "S1") (pin "1") (pinfunction "P_1") (pintype "passive"))
      (node (ref "U$1") (pin "P108") (pinfunction "GND_P108") (pintype "bidirectional"))
      (node (ref "U$1") (pin "P113") (pinfunction "GND_P113") (pintype "bidirectional"))
      (node (ref "U$1") (pin "P13") (pinfunction "GND_P13") (pintype "bidirectional"))
      (node (ref "U$1") (pin "P130") (pinfunction "GND_P130") (pintype "bidirectional"))
      (node (ref "U$1") (pin "P136") (pinfunction "GND_P136") (pintype "bidirectional"))
      (node (ref "U$1") (pin "P25") (pinfunction "GND_P25") (pintype "bidirectional"))
      (node (ref "U$1") (pin "P3") (pinfunction "GND_P3") (pintype "bidirectional"))
      (node (ref "U$1") (pin "P49") (pinfunction "GND_P49") (pintype "bidirectional"))
      (node (ref "U$1") (pin "P54") (pinfunction "GND_P54") (pintype "bidirectional"))
      (node (ref "U$1") (pin "P68") (pinfunction "GND_P68") (pintype "bidirectional"))
      (node (ref "U$1") (pin "P73") (pinfunction "SUSPEND_P73") (pintype "bidirectional"))
      (node (ref "U$1") (pin "P77") (pinfunction "GND_P77") (pintype "bidirectional"))
      (node (ref "U$1") (pin "P91") (pinfunction "GND_P91") (pintype "bidirectional"))
      (node (ref "U$1") (pin "P96") (pinfunction "GND_P96") (pintype "bidirectional"))
      (node (ref "U1") (pin "11") (pinfunction "GND_11") (pintype "power_in"))
      (node (ref "U1") (pin "32") (pinfunction "GND1_32") (pintype "power_in"))
      (node (ref "U1") (pin "62") (pinfunction "GND2_62") (pintype "power_in"))
      (node (ref "U1") (pin "81") (pinfunction "GND3_81") (pintype "power_in"))
      (node (ref "U1") (pin "99") (pinfunction "AGND_99") (pintype "power_in"))
      (node (ref "U2") (pin "16") (pinfunction "VSS_16") (pintype "output"))
      (node (ref "U4") (pin "4") (pinfunction "GND_4") (pintype "bidirectional"))
    )
    (net (code "76") (name "LEDB") (class "Default")
      (node (ref "R3") (pin "1") (pinfunction "1_1") (pintype "passive"))
      (node (ref "U1") (pin "7") (pinfunction "(OC3C/INT5)PE5_7") (pintype "bidirectional"))
    )
    (net (code "77") (name "LEDG") (class "Default")
      (node (ref "R13") (pin "1") (pinfunction "1_1") (pintype "passive"))
      (node (ref "U1") (pin "1") (pinfunction "(OC0B)PG5_1") (pintype "bidirectional"))
    )
    (net (code "78") (name "LEDR") (class "Default")
      (node (ref "R2") (pin "1") (pinfunction "1_1") (pintype "passive"))
      (node (ref "U1") (pin "6") (pinfunction "(OC3B/INT4)PE4_6") (pintype "bidirectional"))
    )
    (net (code "79") (name "LEFT") (class "Default")
      (node (ref "J2") (pin "3") (pinfunction "3_3") (pintype "passive"))
      (node (ref "U$1") (pin "P80") (pinfunction "IO_L46N_1_P80") (pintype "bidirectional"))
    )
    (net (code "80") (name "LE_IL") (class "Default")
      (node (ref "U$1") (pin "P17") (pinfunction "IO_L43P_GCLK23_3_P17") (pintype "bidirectional"))
      (node (ref "U1") (pin "5") (pinfunction "(OC3A/AIN1)PE3_5") (pintype "bidirectional"))
    )
    (net (code "81") (name "MISO") (class "Default")
      (node (ref "JP6") (pin "1") (pinfunction "1_1") (pintype "passive"))
      (node (ref "R1") (pin "1") (pinfunction "1_1") (pintype "passive"))
      (node (ref "U1") (pin "22") (pinfunction "(MISO/PCINT3)PB3_22") (pintype "bidirectional"))
    )
    (net (code "82") (name "MOSI") (class "Default")
      (node (ref "JP6") (pin "4") (pinfunction "4_4") (pintype "passive"))
      (node (ref "R17") (pin "1") (pinfunction "1_1") (pintype "passive"))
      (node (ref "U1") (pin "21") (pinfunction "(MOSI/PCINT2)PB2_21") (pintype "bidirectional"))
    )
    (net (code "83") (name "Net-(IC5-VOUT)") (class "Default")
      (node (ref "C33") (pin "1") (pinfunction "1_1") (pintype "passive"))
      (node (ref "IC5") (pin "2") (pinfunction "VOUT_2") (pintype "output"))
      (node (ref "L2") (pin "1") (pinfunction "1_1") (pintype "passive"))
    )
    (net (code "84") (name "Net-(IC6A-I)") (class "Default")
      (node (ref "IC6") (pin "2") (pinfunction "I_2") (pintype "input"))
      (node (ref "R17") (pin "2") (pinfunction "2_2") (pintype "passive"))
    )
    (net (code "85") (name "Net-(IC6B-I)") (class "Default")
      (node (ref "IC6") (pin "5") (pinfunction "I_5") (pintype "input"))
      (node (ref "R18") (pin "2") (pinfunction "2_2") (pintype "passive"))
    )
    (net (code "86") (name "Net-(IC6C-I)") (class "Default")
      (node (ref "IC6") (pin "9") (pinfunction "I_9") (pintype "input"))
      (node (ref "R21") (pin "2") (pinfunction "2_2") (pintype "passive"))
    )
    (net (code "87") (name "Net-(IC6D-O)") (class "Default")
      (node (ref "IC6") (pin "11") (pinfunction "O_11") (pintype "tri_state"))
      (node (ref "R1") (pin "2") (pinfunction "2_2") (pintype "passive"))
    )
    (net (code "88") (name "Net-(IC7-DTR)") (class "Default")
      (node (ref "C9") (pin "2") (pinfunction "2_2") (pintype "passive"))
      (node (ref "IC7") (pin "13") (pinfunction "DTR_13") (pintype "bidirectional"))
      (node (ref "R26") (pin "1") (pinfunction "1_1") (pintype "passive"))
    )
    (net (code "89") (name "Net-(IC7-RX)") (class "Default")
      (node (ref "IC7") (pin "3") (pinfunction "RX_3") (pintype "bidirectional"))
      (node (ref "R23") (pin "2") (pinfunction "2_2") (pintype "passive"))
    )
    (net (code "90") (name "Net-(IC7-TX)") (class "Default")
      (node (ref "IC7") (pin "2") (pinfunction "TX_2") (pintype "bidirectional"))
      (node (ref "R22") (pin "2") (pinfunction "2_2") (pintype "passive"))
    )
    (net (code "91") (name "Net-(IC7-V3)") (class "Default")
      (node (ref "C8") (pin "2") (pinfunction "2_2") (pintype "passive"))
      (node (ref "IC7") (pin "4") (pinfunction "V3_4") (pintype "bidirectional"))
    )
    (net (code "92") (name "Net-(IC7-XI)") (class "Default")
      (node (ref "C20") (pin "2") (pinfunction "2_2") (pintype "passive"))
      (node (ref "IC7") (pin "7") (pinfunction "XI_7") (pintype "bidirectional"))
      (node (ref "Q2") (pin "3") (pinfunction "2_3") (pintype "passive"))
      (node (ref "R27") (pin "2") (pinfunction "2_2") (pintype "passive"))
    )
    (net (code "93") (name "Net-(IC7-XO)") (class "Default")
      (node (ref "C21") (pin "2") (pinfunction "2_2") (pintype "passive"))
      (node (ref "IC7") (pin "8") (pinfunction "XO_8") (pintype "bidirectional"))
      (node (ref "Q2") (pin "1") (pinfunction "1_1") (pintype "passive"))
      (node (ref "R27") (pin "1") (pinfunction "1_1") (pintype "passive"))
    )
    (net (code "94") (name "Net-(J1-D+)") (class "Default")
      (node (ref "J1") (pin "3") (pinfunction "D+_3") (pintype "bidirectional"))
      (node (ref "R29") (pin "2") (pinfunction "2_2") (pintype "passive"))
    )
    (net (code "95") (name "Net-(J1-D-)") (class "Default")
      (node (ref "J1") (pin "2") (pinfunction "D-_2") (pintype "bidirectional"))
      (node (ref "R28") (pin "2") (pinfunction "2_2") (pintype "passive"))
    )
    (net (code "96") (name "Net-(LED2-PadA)") (class "Default")
      (node (ref "LED2") (pin "A") (pinfunction "A_A") (pintype "passive"))
      (node (ref "R11") (pin "2") (pinfunction "2_2") (pintype "passive"))
    )
    (net (code "97") (name "Net-(LED3A-A)") (class "Default")
      (node (ref "LED3") (pin "P6") (pinfunction "A_P6") (pintype "passive"))
      (node (ref "R3") (pin "2") (pinfunction "2_2") (pintype "passive"))
    )
    (net (code "98") (name "Net-(LED3B-A)") (class "Default")
      (node (ref "LED3") (pin "P5") (pinfunction "A_P5") (pintype "passive"))
      (node (ref "R13") (pin "2") (pinfunction "2_2") (pintype "passive"))
    )
    (net (code "99") (name "Net-(LED3C-A)") (class "Default")
      (node (ref "LED3") (pin "P4") (pinfunction "A_P4") (pintype "passive"))
      (node (ref "R2") (pin "2") (pinfunction "2_2") (pintype "passive"))
    )
    (net (code "100") (name "Net-(MICRO_SD1-DAT0)") (class "Default")
      (node (ref "MICRO_SD1") (pin "7") (pinfunction "DAT0_7") (pintype "bidirectional"))
      (node (ref "R20") (pin "2") (pinfunction "2_2") (pintype "passive"))
    )
    (net (code "101") (name "Net-(PAD2-P)") (class "Default")
      (node (ref "PAD2") (pin "1") (pinfunction "P_1") (pintype "passive"))
      (node (ref "U1") (pin "27") (pinfunction "PH7(T4)_27") (pintype "bidirectional"))
    )
    (net (code "102") (name "Net-(PAD3-P)") (class "Default")
      (node (ref "PAD3") (pin "1") (pinfunction "P_1") (pintype "passive"))
      (node (ref "U1") (pin "28") (pinfunction "(TOSC2)PG3_28") (pintype "bidirectional"))
    )
    (net (code "103") (name "Net-(Q1-2)") (class "Default")
      (node (ref "C16") (pin "2") (pinfunction "2_2") (pintype "passive"))
      (node (ref "Q1") (pin "3") (pinfunction "2_3") (pintype "passive"))
      (node (ref "R19") (pin "2") (pinfunction "2_2") (pintype "passive"))
      (node (ref "U1") (pin "33") (pinfunction "XTAL2_33") (pintype "output"))
    )
    (net (code "104") (name "Net-(U$1-IO_L49N_D4_2)") (class "Default")
      (node (ref "SJ2") (pin "1") (pinfunction "1_1") (pintype "passive"))
      (node (ref "U$1") (pin "P45") (pinfunction "IO_L49N_D4_2_P45") (pintype "bidirectional"))
    )
    (net (code "105") (name "Net-(U$1-PROGRAM_B_2)") (class "Default")
      (node (ref "R12") (pin "2") (pinfunction "2_2") (pintype "passive"))
      (node (ref "U$1") (pin "P37") (pinfunction "PROGRAM_B_2_P37") (pintype "bidirectional"))
    )
    (net (code "106") (name "Net-(U1-XTAL1)") (class "Default")
      (node (ref "C17") (pin "2") (pinfunction "2_2") (pintype "passive"))
      (node (ref "Q1") (pin "1") (pinfunction "1_1") (pintype "passive"))
      (node (ref "R19") (pin "1") (pinfunction "1_1") (pintype "passive"))
      (node (ref "U1") (pin "34") (pinfunction "XTAL1_34") (pintype "input"))
    )
    (net (code "107") (name "O0") (class "Default")
      (node (ref "U$1") (pin "P127") (pinfunction "IO_L36P_GCLK15_0_P127") (pintype "bidirectional"))
      (node (ref "U1") (pin "89") (pinfunction "PK0(ADC8/PCINT16)_89") (pintype "bidirectional"))
    )
    (net (code "108") (name "O1") (class "Default")
      (node (ref "U$1") (pin "P131") (pinfunction "IO_L35N_GCLK16_0_P131") (pintype "bidirectional"))
      (node (ref "U1") (pin "88") (pinfunction "PK1(ADC9/PCINT17)_88") (pintype "bidirectional"))
    )
    (net (code "109") (name "O2") (class "Default")
      (node (ref "U$1") (pin "P132") (pinfunction "IO_L35P_GCLK17_0_P132") (pintype "bidirectional"))
      (node (ref "U1") (pin "87") (pinfunction "PK2(ADC10/PCINT18)_87") (pintype "bidirectional"))
    )
    (net (code "110") (name "O3") (class "Default")
      (node (ref "U$1") (pin "P133") (pinfunction "IO_L34N_GCLK18_0_P133") (pintype "bidirectional"))
      (node (ref "U1") (pin "86") (pinfunction "PK3(ADC11/PCINT19)_86") (pintype "bidirectional"))
    )
    (net (code "111") (name "O4") (class "Default")
      (node (ref "U$1") (pin "P134") (pinfunction "IO_L34P_GCLK19_0_P134") (pintype "bidirectional"))
      (node (ref "U1") (pin "85") (pinfunction "PK4(ADC12/PCINT20)_85") (pintype "bidirectional"))
    )
    (net (code "112") (name "O5") (class "Default")
      (node (ref "U$1") (pin "P137") (pinfunction "IO_L4N_0_P137") (pintype "bidirectional"))
      (node (ref "U1") (pin "84") (pinfunction "PK5(ADC13/PCINT21)_84") (pintype "bidirectional"))
    )
    (net (code "113") (name "O6") (class "Default")
      (node (ref "U$1") (pin "P138") (pinfunction "IO_L4P_0_P138") (pintype "bidirectional"))
      (node (ref "U1") (pin "83") (pinfunction "PK6(ADC14/PCINT22)_83") (pintype "bidirectional"))
    )
    (net (code "114") (name "O7") (class "Default")
      (node (ref "U$1") (pin "P139") (pinfunction "IO_L3N_0_P139") (pintype "bidirectional"))
      (node (ref "U1") (pin "82") (pinfunction "PK7(ADC15/PCINT23)_82") (pintype "bidirectional"))
    )
    (net (code "115") (name "PAGE_A8") (class "Default")
      (node (ref "U$1") (pin "P93") (pinfunction "IO_L41P_GCLK9_IRDY1_1_P93") (pintype "bidirectional"))
      (node (ref "U1") (pin "41") (pinfunction "PL6_41") (pintype "bidirectional"))
    )
    (net (code "116") (name "RAMBUF_OE") (class "Default")
      (node (ref "U$1") (pin "P144") (pinfunction "IO_L1P_HSWAPEN_0_P144") (pintype "bidirectional"))
      (node (ref "U1") (pin "16") (pinfunction "PH4(OC4B)_16") (pintype "bidirectional"))
    )
    (net (code "117") (name "RD+") (class "Default")
      (node (ref "IC7") (pin "5") (pinfunction "D+_5") (pintype "bidirectional"))
      (node (ref "R29") (pin "1") (pinfunction "1_1") (pintype "passive"))
    )
    (net (code "118") (name "RD-") (class "Default")
      (node (ref "IC7") (pin "6") (pinfunction "D-_6") (pintype "bidirectional"))
      (node (ref "R28") (pin "1") (pinfunction "1_1") (pintype "passive"))
    )
    (net (code "119") (name "RESET") (class "Default")
      (node (ref "C5") (pin "2") (pinfunction "2_2") (pintype "passive"))
      (node (ref "C9") (pin "1") (pinfunction "1_1") (pintype "passive"))
      (node (ref "D1") (pin "A") (pinfunction "A_A") (pintype "passive"))
      (node (ref "JP6") (pin "5") (pinfunction "5_5") (pintype "passive"))
      (node (ref "R15") (pin "1") (pinfunction "1_1") (pintype "passive"))
      (node (ref "S1") (pin "2") (pinfunction "S_2") (pintype "passive"))
      (node (ref "U1") (pin "30") (pinfunction "RESET_30") (pintype "input"))
    )
    (net (code "120") (name "RIGHT") (class "Default")
      (node (ref "J2") (pin "4") (pinfunction "4_4") (pintype "passive"))
      (node (ref "U$1") (pin "P81") (pinfunction "IO_L46P_1_P81") (pintype "bidirectional"))
    )
    (net (code "121") (name "ROM_WR_EN") (class "Default")
      (node (ref "U$1") (pin "P92") (pinfunction "IO_L41N_GCLK8_1_P92") (pintype "bidirectional"))
      (node (ref "U1") (pin "36") (pinfunction "PL1(ICP5)_36") (pintype "bidirectional"))
    )
    (net (code "122") (name "RST_CTRL_REG") (class "Default")
      (node (ref "U$1") (pin "P95") (pinfunction "IO_L40P_GCLK11_1_P95") (pintype "bidirectional"))
      (node (ref "U1") (pin "26") (pinfunction "(OC0A/OC1C/PCINT7)PB7_26") (pintype "bidirectional"))
    )
    (net (code "123") (name "RST_DATA_REG") (class "Default")
      (node (ref "U$1") (pin "P94") (pinfunction "IO_L40N_GCLK10_1_P94") (pintype "bidirectional"))
      (node (ref "U1") (pin "63") (pinfunction "PJ0(RXD3/PCINT9)_63") (pintype "bidirectional"))
    )
    (net (code "124") (name "RX0") (class "Default")
      (node (ref "R23") (pin "1") (pinfunction "1_1") (pintype "passive"))
      (node (ref "U1") (pin "3") (pinfunction "(TXD0)PE1_3") (pintype "bidirectional"))
    )
    (net (code "125") (name "SCK_LLS") (class "Default")
      (node (ref "IC6") (pin "6") (pinfunction "O_6") (pintype "tri_state"))
      (node (ref "MICRO_SD1") (pin "5") (pinfunction "CLK_5") (pintype "bidirectional"))
    )
    (net (code "126") (name "SCL") (class "Default")
      (node (ref "IC10") (pin "5") (pinfunction "SCL_5") (pintype "passive"))
      (node (ref "U1") (pin "43") (pinfunction "(SCL/INT0)PD0_43") (pintype "bidirectional"))
    )
    (net (code "127") (name "SCLK") (class "Default")
      (node (ref "JP6") (pin "3") (pinfunction "3_3") (pintype "passive"))
      (node (ref "R18") (pin "1") (pinfunction "1_1") (pintype "passive"))
      (node (ref "U1") (pin "20") (pinfunction "(SCK/PCINT1)PB1_20") (pintype "bidirectional"))
    )
    (net (code "128") (name "SDA") (class "Default")
      (node (ref "IC10") (pin "4") (pinfunction "SDA_4") (pintype "passive"))
      (node (ref "U1") (pin "44") (pinfunction "(SDA/INT1)PD1_44") (pintype "bidirectional"))
    )
    (net (code "129") (name "SD_LED") (class "Default")
      (node (ref "LED2") (pin "C") (pinfunction "C_C") (pintype "passive"))
      (node (ref "U1") (pin "37") (pinfunction "PL2(T5)_37") (pintype "bidirectional"))
    )
    (net (code "130") (name "SEL_128CHARS") (class "Default")
      (node (ref "U$1") (pin "P88") (pinfunction "IO_L42P_GCLK7_1_P88") (pintype "bidirectional"))
      (node (ref "U1") (pin "35") (pinfunction "PL0(ICP4)_35") (pintype "bidirectional"))
    )
    (net (code "131") (name "SPARE1") (class "Default")
      (node (ref "U1") (pin "38") (pinfunction "PL3(OC5A)_38") (pintype "bidirectional"))
    )
    (net (code "132") (name "SPEAKER") (class "Default")
      (node (ref "IC10") (pin "1") (pinfunction "VOUT_1") (pintype "passive"))
      (node (ref "JP1") (pin "2") (pinfunction "2_2") (pintype "passive"))
    )
    (net (code "133") (name "SS_SD") (class "Default")
      (node (ref "R21") (pin "1") (pinfunction "1_1") (pintype "passive"))
      (node (ref "U1") (pin "19") (pinfunction "(SS/PCINT0)PB0_19") (pintype "bidirectional"))
    )
    (net (code "134") (name "TCK") (class "Default")
      (node (ref "JP3") (pin "1") (pinfunction "1_1") (pintype "passive"))
      (node (ref "R7") (pin "2") (pinfunction "2_2") (pintype "passive"))
      (node (ref "R8") (pin "2") (pinfunction "2_2") (pintype "passive"))
      (node (ref "U$1") (pin "P109") (pinfunction "TCK_P109") (pintype "bidirectional"))
    )
    (net (code "135") (name "TCK'") (class "Default")
      (node (ref "R7") (pin "1") (pinfunction "1_1") (pintype "passive"))
      (node (ref "U1") (pin "24") (pinfunction "(OC1A/PCINT5)PB5_24") (pintype "bidirectional"))
    )
    (net (code "136") (name "TDI") (class "Default")
      (node (ref "JP3") (pin "3") (pinfunction "3_3") (pintype "passive"))
      (node (ref "R5") (pin "2") (pinfunction "2_2") (pintype "passive"))
      (node (ref "R9") (pin "2") (pinfunction "2_2") (pintype "passive"))
      (node (ref "U$1") (pin "P110") (pinfunction "TDI_P110") (pintype "bidirectional"))
    )
    (net (code "137") (name "TDI'") (class "Default")
      (node (ref "R5") (pin "1") (pinfunction "1_1") (pintype "passive"))
      (node (ref "U1") (pin "18") (pinfunction "PH6(OC2B)_18") (pintype "bidirectional"))
    )
    (net (code "138") (name "TDO") (class "Default")
      (node (ref "JP3") (pin "2") (pinfunction "2_2") (pintype "passive"))
      (node (ref "R6") (pin "2") (pinfunction "2_2") (pintype "passive"))
      (node (ref "U$1") (pin "P106") (pinfunction "TDO_P106") (pintype "bidirectional"))
    )
    (net (code "139") (name "TDO'") (class "Default")
      (node (ref "R6") (pin "1") (pinfunction "1_1") (pintype "passive"))
      (node (ref "U1") (pin "17") (pinfunction "PH5(OC4C)_17") (pintype "bidirectional"))
    )
    (net (code "140") (name "TMS") (class "Default")
      (node (ref "JP3") (pin "4") (pinfunction "4_4") (pintype "passive"))
      (node (ref "R10") (pin "2") (pinfunction "2_2") (pintype "passive"))
      (node (ref "R4") (pin "2") (pinfunction "2_2") (pintype "passive"))
      (node (ref "U$1") (pin "P107") (pinfunction "TMS_P107") (pintype "bidirectional"))
    )
    (net (code "141") (name "TMS'") (class "Default")
      (node (ref "R4") (pin "1") (pinfunction "1_1") (pintype "passive"))
      (node (ref "U1") (pin "23") (pinfunction "(OC2A/PCINT4)PB4_23") (pintype "bidirectional"))
    )
    (net (code "142") (name "TX0") (class "Default")
      (node (ref "R22") (pin "1") (pinfunction "1_1") (pintype "passive"))
      (node (ref "U1") (pin "2") (pinfunction "(RXD0/PCIN8)PE0_2") (pintype "bidirectional"))
    )
    (net (code "143") (name "UP") (class "Default")
      (node (ref "J2") (pin "1") (pinfunction "1_1") (pintype "passive"))
      (node (ref "U$1") (pin "P78") (pinfunction "IO_L47N_1_P78") (pintype "bidirectional"))
    )
    (net (code "144") (name "VCC") (class "Default")
      (node (ref "C1") (pin "1") (pinfunction "1_1") (pintype "passive"))
      (node (ref "C13") (pin "1") (pinfunction "1_1") (pintype "passive"))
      (node (ref "C14") (pin "1") (pinfunction "1_1") (pintype "passive"))
      (node (ref "C15") (pin "1") (pinfunction "1_1") (pintype "passive"))
      (node (ref "C19") (pin "1") (pinfunction "1_1") (pintype "passive"))
      (node (ref "C2") (pin "1") (pinfunction "1_1") (pintype "passive"))
      (node (ref "C3") (pin "1") (pinfunction "1_1") (pintype "passive"))
      (node (ref "C32") (pin "1") (pinfunction "1_1") (pintype "passive"))
      (node (ref "D1") (pin "C") (pinfunction "C_C") (pintype "passive"))
      (node (ref "IC1") (pin "2") (pinfunction "VO_2") (pintype "passive"))
      (node (ref "IC10") (pin "3") (pinfunction "VDD_3") (pintype "passive"))
      (node (ref "IC2") (pin "3") (pinfunction "VIN_3") (pintype "input"))
      (node (ref "IC5") (pin "3") (pinfunction "VIN_3") (pintype "input"))
      (node (ref "IC7") (pin "16") (pinfunction "VCC_16") (pintype "bidirectional"))
      (node (ref "J1") (pin "1") (pinfunction "VBUS_1") (pintype "power_in"))
      (node (ref "JP6") (pin "2") (pinfunction "2_2") (pintype "passive"))
      (node (ref "R11") (pin "1") (pinfunction "1_1") (pintype "passive"))
      (node (ref "R15") (pin "2") (pinfunction "2_2") (pintype "passive"))
      (node (ref "SJ1") (pin "2") (pinfunction "2_2") (pintype "passive"))
      (node (ref "U1") (pin "10") (pinfunction "VCC_10") (pintype "power_in"))
      (node (ref "U1") (pin "100") (pinfunction "AVCC_100") (pintype "power_in"))
      (node (ref "U1") (pin "31") (pinfunction "VCC1_31") (pintype "power_in"))
      (node (ref "U1") (pin "61") (pinfunction "VCC2_61") (pintype "power_in"))
      (node (ref "U1") (pin "80") (pinfunction "VCC3_80") (pintype "power_in"))
      (node (ref "U2") (pin "32") (pinfunction "VCC_32") (pintype "power_in"))
    )
    (net (code "145") (name "unconnected-(IC7-CTS-Pad9)") (class "Default")
      (node (ref "IC7") (pin "9") (pinfunction "CTS_9") (pintype "bidirectional"))
    )
    (net (code "146") (name "unconnected-(IC7-DCD-Pad12)") (class "Default")
      (node (ref "IC7") (pin "12") (pinfunction "DCD_12") (pintype "bidirectional"))
    )
    (net (code "147") (name "unconnected-(IC7-DSR-Pad10)") (class "Default")
      (node (ref "IC7") (pin "10") (pinfunction "DSR_10") (pintype "bidirectional"))
    )
    (net (code "148") (name "unconnected-(IC7-RI-Pad11)") (class "Default")
      (node (ref "IC7") (pin "11") (pinfunction "RI_11") (pintype "bidirectional"))
    )
    (net (code "149") (name "unconnected-(IC7-RS232-Pad15)") (class "Default")
      (node (ref "IC7") (pin "15") (pinfunction "RS232_15") (pintype "bidirectional"))
    )
    (net (code "150") (name "unconnected-(IC7-RTS-Pad14)") (class "Default")
      (node (ref "IC7") (pin "14") (pinfunction "RTS_14") (pintype "bidirectional"))
    )
    (net (code "151") (name "unconnected-(J1-ID-Pad4)") (class "Default")
      (node (ref "J1") (pin "4") (pinfunction "ID_4") (pintype "bidirectional"))
    )
    (net (code "152") (name "unconnected-(J2-Pad5)") (class "Default")
      (node (ref "J2") (pin "5") (pinfunction "5_5") (pintype "passive"))
    )
    (net (code "153") (name "unconnected-(J2-Pad7)") (class "Default")
      (node (ref "J2") (pin "7") (pinfunction "7_7") (pintype "passive"))
    )
    (net (code "154") (name "unconnected-(J2-Pad9)") (class "Default")
      (node (ref "J2") (pin "9") (pinfunction "9_9") (pintype "passive"))
    )
    (net (code "155") (name "unconnected-(MICRO_SD1-CD-PadCD1)") (class "Default")
      (node (ref "MICRO_SD1") (pin "CD1") (pinfunction "CD_CD1") (pintype "passive"))
    )
    (net (code "156") (name "unconnected-(MICRO_SD1-DAT1-Pad8)") (class "Default")
      (node (ref "MICRO_SD1") (pin "8") (pinfunction "DAT1_8") (pintype "bidirectional"))
    )
    (net (code "157") (name "unconnected-(MICRO_SD1-DAT2-Pad1)") (class "Default")
      (node (ref "MICRO_SD1") (pin "1") (pinfunction "DAT2_1") (pintype "bidirectional"))
    )
    (net (code "158") (name "unconnected-(U$1-CMPCS_B_2-PadP72)") (class "Default")
      (node (ref "U$1") (pin "P72") (pinfunction "CMPCS_B_2_P72") (pintype "bidirectional"))
    )
    (net (code "159") (name "unconnected-(U$1-DONE_2-PadP71)") (class "Default")
      (node (ref "U$1") (pin "P71") (pinfunction "DONE_2_P71") (pintype "bidirectional"))
    )
    (net (code "160") (name "unconnected-(U$1-IO_L2N_0-PadP141)") (class "Default")
      (node (ref "U$1") (pin "P141") (pinfunction "IO_L2N_0_P141") (pintype "bidirectional"))
    )
    (net (code "161") (name "unconnected-(U$1-IO_L2P_0-PadP142)") (class "Default")
      (node (ref "U$1") (pin "P142") (pinfunction "IO_L2P_0_P142") (pintype "bidirectional"))
    )
    (net (code "162") (name "unconnected-(U1-(CLKO{slash}ICP3{slash}INT7)PE7-Pad9)") (class "Default")
      (node (ref "U1") (pin "9") (pinfunction "(CLKO/ICP3/INT7)PE7_9") (pintype "bidirectional"))
    )
    (net (code "163") (name "unconnected-(U1-(T1)PD6-Pad49)") (class "Default")
      (node (ref "U1") (pin "49") (pinfunction "(T1)PD6_49") (pintype "bidirectional"))
    )
    (net (code "164") (name "unconnected-(U1-(T3{slash}INT6)PE6-Pad8)") (class "Default")
      (node (ref "U1") (pin "8") (pinfunction "(T3/INT6)PE6_8") (pintype "bidirectional"))
    )
    (net (code "165") (name "unconnected-(U1-(TOSC1)PG4-Pad29)") (class "Default")
      (node (ref "U1") (pin "29") (pinfunction "(TOSC1)PG4_29") (pintype "bidirectional"))
    )
    (net (code "166") (name "unconnected-(U1-(XCK0{slash}AIN0)PE2-Pad4)") (class "Default")
      (node (ref "U1") (pin "4") (pinfunction "(XCK0/AIN0)PE2_4") (pintype "bidirectional"))
    )
    (net (code "167") (name "unconnected-(U1-PH2(XCK2)-Pad14)") (class "Default")
      (node (ref "U1") (pin "14") (pinfunction "PH2(XCK2)_14") (pintype "bidirectional"))
    )
    (net (code "168") (name "unconnected-(U1-PJ2(XCK3{slash}PCINT11)-Pad65)") (class "Default")
      (node (ref "U1") (pin "65") (pinfunction "PJ2(XCK3/PCINT11)_65") (pintype "bidirectional"))
    )
    (net (code "169") (name "unconnected-(U1-PJ3(PCINT12)-Pad66)") (class "Default")
      (node (ref "U1") (pin "66") (pinfunction "PJ3(PCINT12)_66") (pintype "bidirectional"))
    )
    (net (code "170") (name "unconnected-(U1-PJ4(PCINT13)-Pad67)") (class "Default")
      (node (ref "U1") (pin "67") (pinfunction "PJ4(PCINT13)_67") (pintype "bidirectional"))
    )
    (net (code "171") (name "{slash}BUSAK") (class "Default")
      (node (ref "18A") (pin "1") (pinfunction "P_1") (pintype "passive"))
    )
    (net (code "172") (name "{slash}BUSRQ") (class "Default")
      (node (ref "20A") (pin "1") (pinfunction "P_1") (pintype "passive"))
    )
    (net (code "173") (name "{slash}CLOCK") (class "Default")
      (node (ref "6B") (pin "1") (pinfunction "P_1") (pintype "passive"))
      (node (ref "U$1") (pin "P87") (pinfunction "IO_L42N_GCLK6_TRDY1_1_P87") (pintype "bidirectional"))
    )
    (net (code "174") (name "{slash}HALT") (class "Default")
      (node (ref "13A") (pin "1") (pinfunction "P_1") (pintype "passive"))
      (node (ref "SJ2") (pin "2") (pinfunction "2_2") (pintype "passive"))
    )
    (net (code "175") (name "{slash}IORQ") (class "Default")
      (node (ref "15A") (pin "1") (pinfunction "P_1") (pintype "passive"))
      (node (ref "U$1") (pin "P50") (pinfunction "IO_L31N_GCLK30_D15_2_P50") (pintype "bidirectional"))
    )
    (net (code "176") (name "{slash}M1") (class "Default")
      (node (ref "22A") (pin "1") (pinfunction "P_1") (pintype "passive"))
      (node (ref "U$1") (pin "P69") (pinfunction "IO_L1N_M0_CMPMISO_2_P69") (pintype "bidirectional"))
    )
    (net (code "177") (name "{slash}MEM_CE") (class "Default")
      (node (ref "U$1") (pin "P115") (pinfunction "IO_L65P_SCP3_0_P115") (pintype "bidirectional"))
      (node (ref "U1") (pin "50") (pinfunction "(T0)PD7_50") (pintype "bidirectional"))
      (node (ref "U2") (pin "22") (pinfunction "CE_22") (pintype "input"))
    )
    (net (code "178") (name "{slash}MEM_OE") (class "Default")
      (node (ref "U$1") (pin "P12") (pinfunction "IO_L49P_3_P12") (pintype "bidirectional"))
      (node (ref "U1") (pin "52") (pinfunction "(RD)PG1_52") (pintype "bidirectional"))
      (node (ref "U2") (pin "24") (pinfunction "OE_24") (pintype "input"))
    )
    (net (code "179") (name "{slash}MREQ") (class "Default")
      (node (ref "14A") (pin "1") (pinfunction "P_1") (pintype "passive"))
      (node (ref "U$1") (pin "P47") (pinfunction "IO_L48N_RDWR_B_VREF_2_P47") (pintype "bidirectional"))
    )
    (net (code "180") (name "{slash}NMI") (class "Default")
      (node (ref "12A") (pin "1") (pinfunction "P_1") (pintype "passive"))
      (node (ref "U$1") (pin "P43") (pinfunction "IO_L62N_D6_2_P43") (pintype "bidirectional"))
    )
    (net (code "181") (name "{slash}OE_OL") (class "Default")
      (node (ref "U$1") (pin "P16") (pinfunction "IO_L43N_GCLK22_IRDY2_3_P16") (pintype "bidirectional"))
      (node (ref "U1") (pin "13") (pinfunction "PH1(TXD2)_13") (pintype "bidirectional"))
    )
    (net (code "182") (name "{slash}RAMCS") (class "Default")
      (node (ref "2A") (pin "1") (pinfunction "P_1") (pintype "passive"))
      (node (ref "U$1") (pin "P22") (pinfunction "IO_L42P_GCLK25_TRDY2_3_P22") (pintype "bidirectional"))
    )
    (net (code "183") (name "{slash}RD") (class "Default")
      (node (ref "16A") (pin "1") (pinfunction "P_1") (pintype "passive"))
      (node (ref "U$1") (pin "P55") (pinfunction "IO_L30N_GCLK0_USERCCLK_2_P55") (pintype "bidirectional"))
    )
    (net (code "184") (name "{slash}RESET") (class "Default")
      (node (ref "21A") (pin "1") (pinfunction "P_1") (pintype "passive"))
      (node (ref "U$1") (pin "P83") (pinfunction "IO_L45P_1_P83") (pintype "bidirectional"))
      (node (ref "U1") (pin "15") (pinfunction "PH3(OC4A)_15") (pintype "bidirectional"))
    )
    (net (code "185") (name "{slash}RFSH") (class "Default")
      (node (ref "23A") (pin "1") (pinfunction "P_1") (pintype "passive"))
      (node (ref "U$1") (pin "P75") (pinfunction "IO_L74P_AWAKE_1_P75") (pintype "bidirectional"))
    )
    (net (code "186") (name "{slash}ROMCS") (class "Default")
      (node (ref "23B") (pin "1") (pinfunction "P_1") (pintype "passive"))
      (node (ref "U$1") (pin "P15") (pinfunction "IO_L44P_GCLK21_3_P15") (pintype "bidirectional"))
    )
    (net (code "187") (name "{slash}WAIT") (class "Default")
      (node (ref "19A") (pin "1") (pinfunction "P_1") (pintype "passive"))
      (node (ref "U$1") (pin "P61") (pinfunction "IO_L12N_D2_MISO3_2_P61") (pintype "bidirectional"))
      (node (ref "U1") (pin "42") (pinfunction "PL7_42") (pintype "bidirectional"))
    )
    (net (code "188") (name "{slash}WR") (class "Default")
      (node (ref "17A") (pin "1") (pinfunction "P_1") (pintype "passive"))
      (node (ref "U$1") (pin "P58") (pinfunction "IO_L14P_D11_2_P58") (pintype "bidirectional"))
    )
    (net (code "189") (name "{slash}WR'") (class "Default")
      (node (ref "U$1") (pin "P14") (pinfunction "IO_L44N_GCLK20_3_P14") (pintype "bidirectional"))
      (node (ref "U1") (pin "51") (pinfunction "(WR)PG0_51") (pintype "bidirectional"))
      (node (ref "U2") (pin "29") (pinfunction "WE_29") (pintype "input"))
    )
  )
)
